# PIX_SH_V3D.net
KiCad netlist of a schematic drawn in Altium Designer
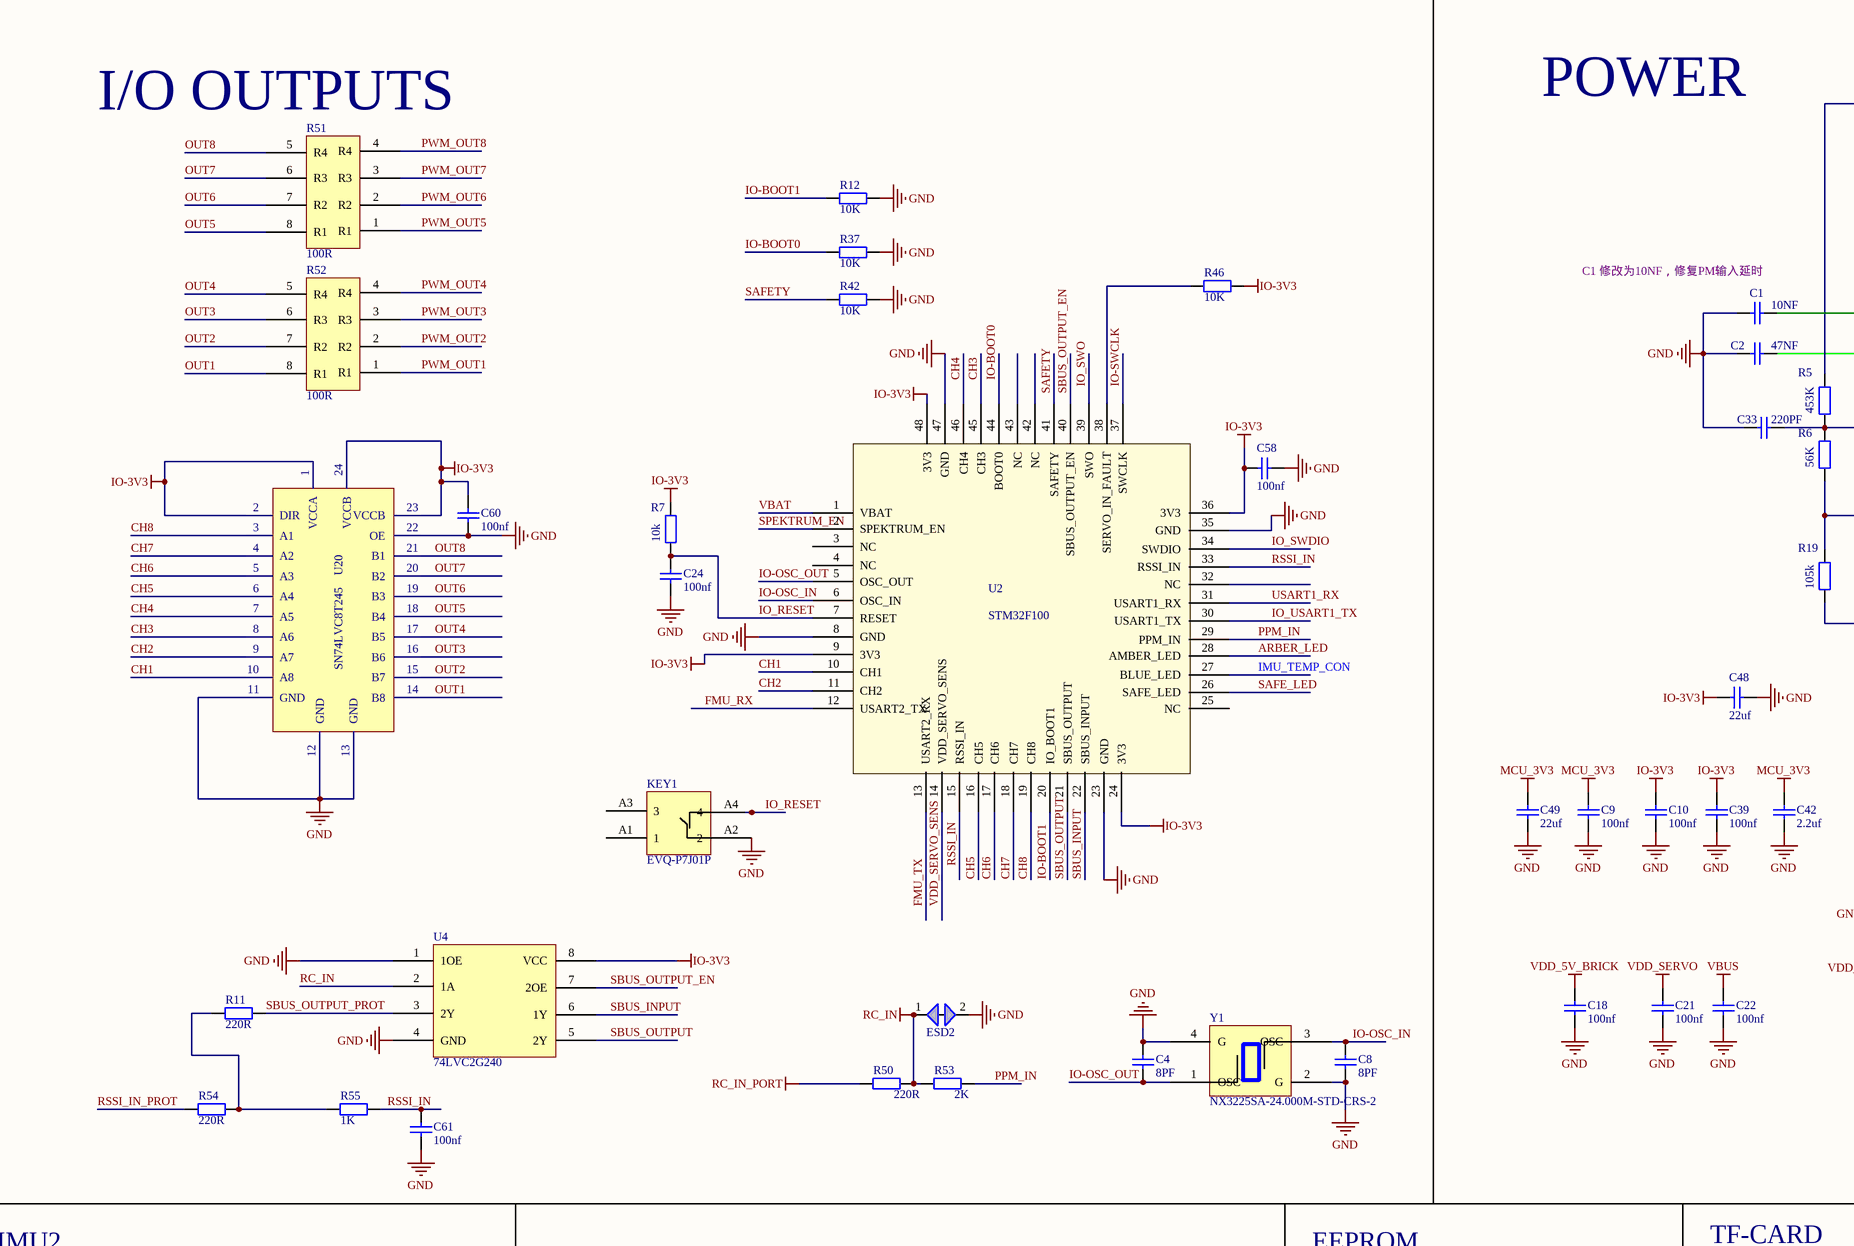
[diagram p0: PIX_SH_V3D.SchDoc, top left]
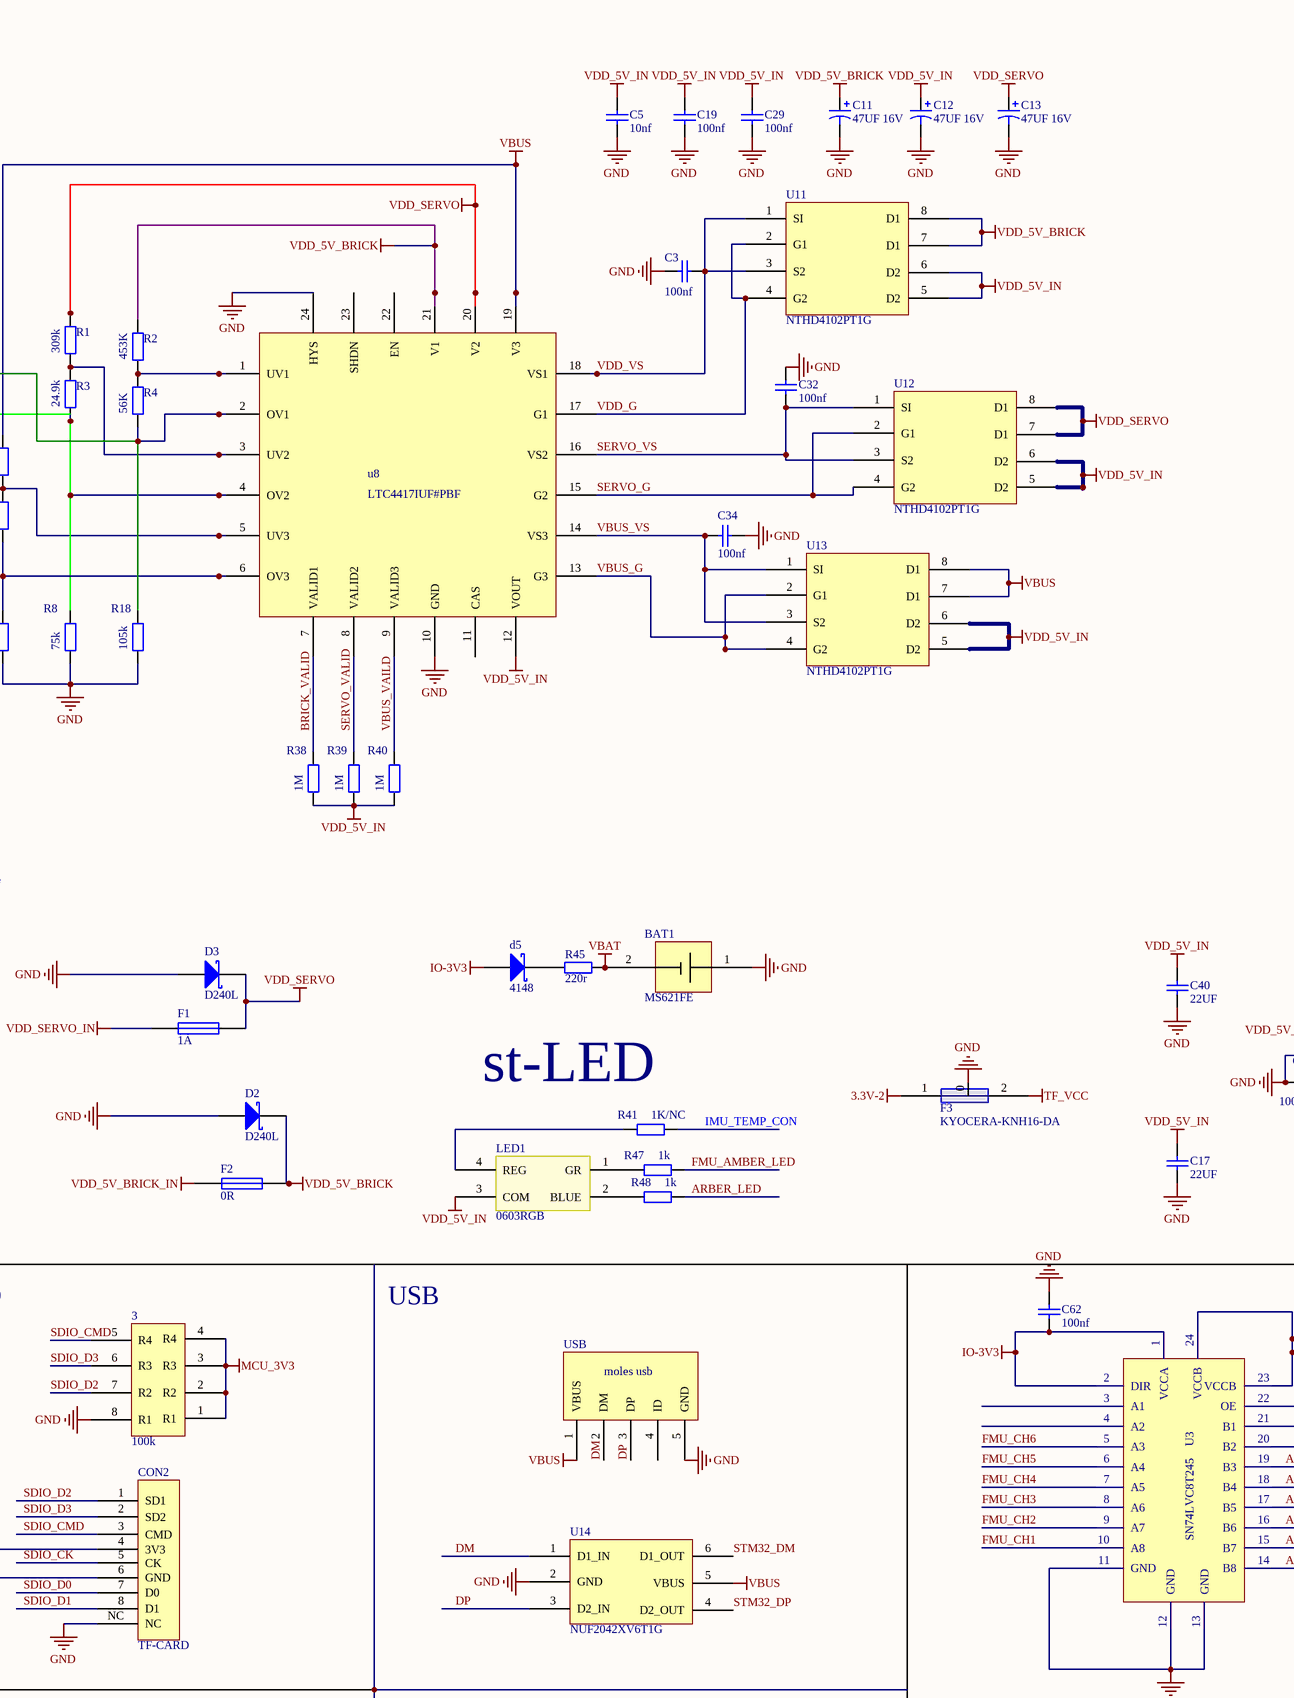
[diagram p1: PIX_SH_V3D.SchDoc, top middle]
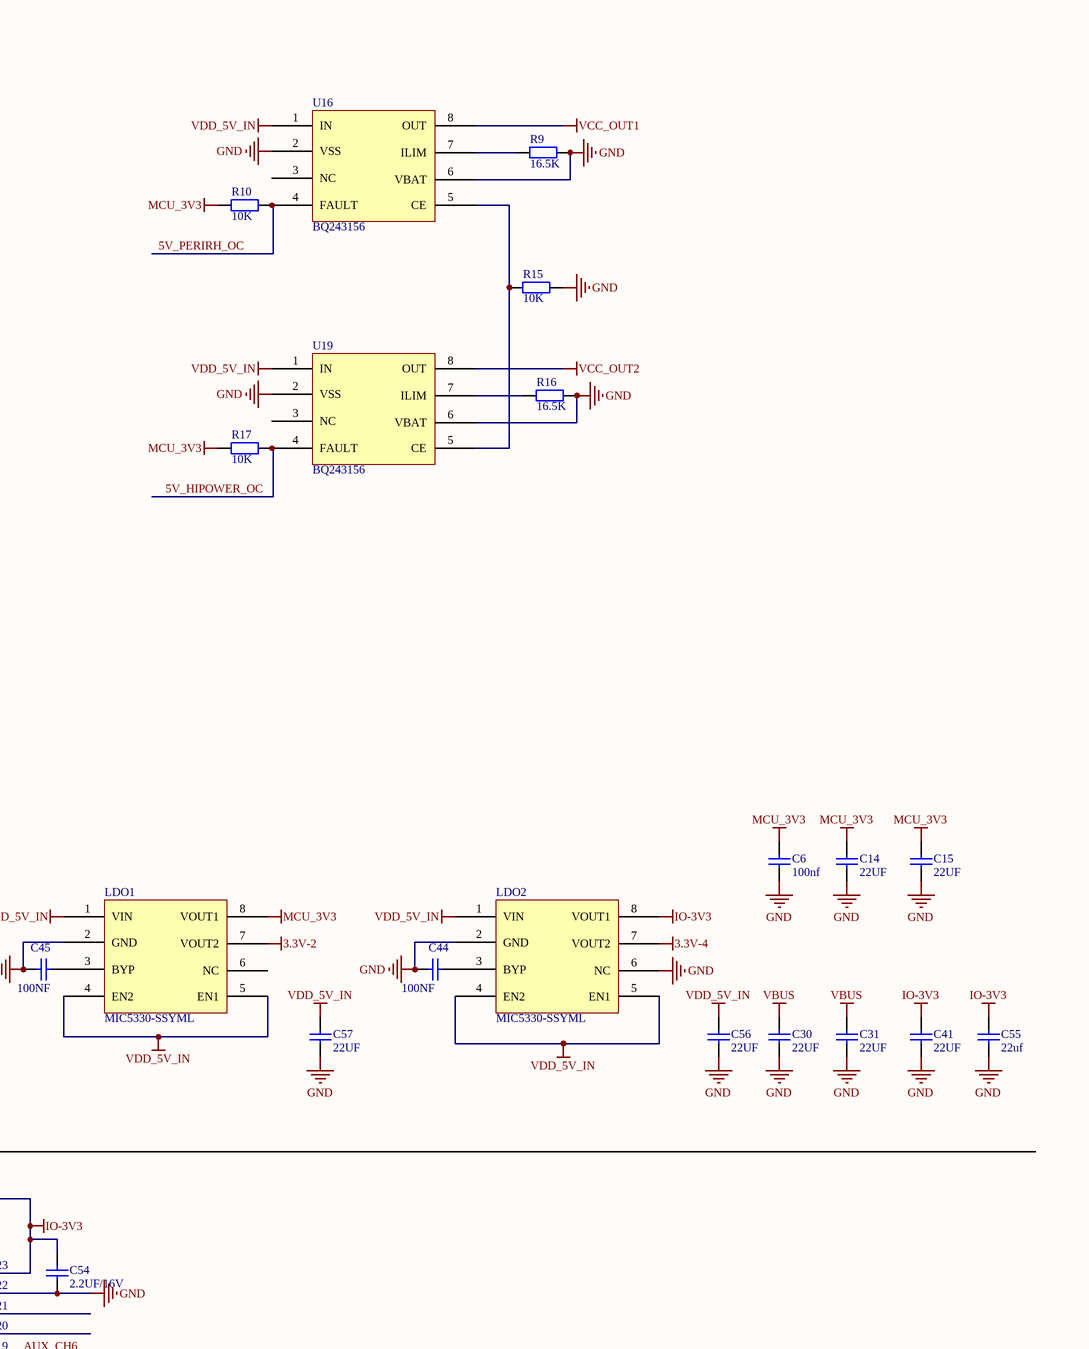
[diagram p2: PIX_SH_V3D.SchDoc, top right]
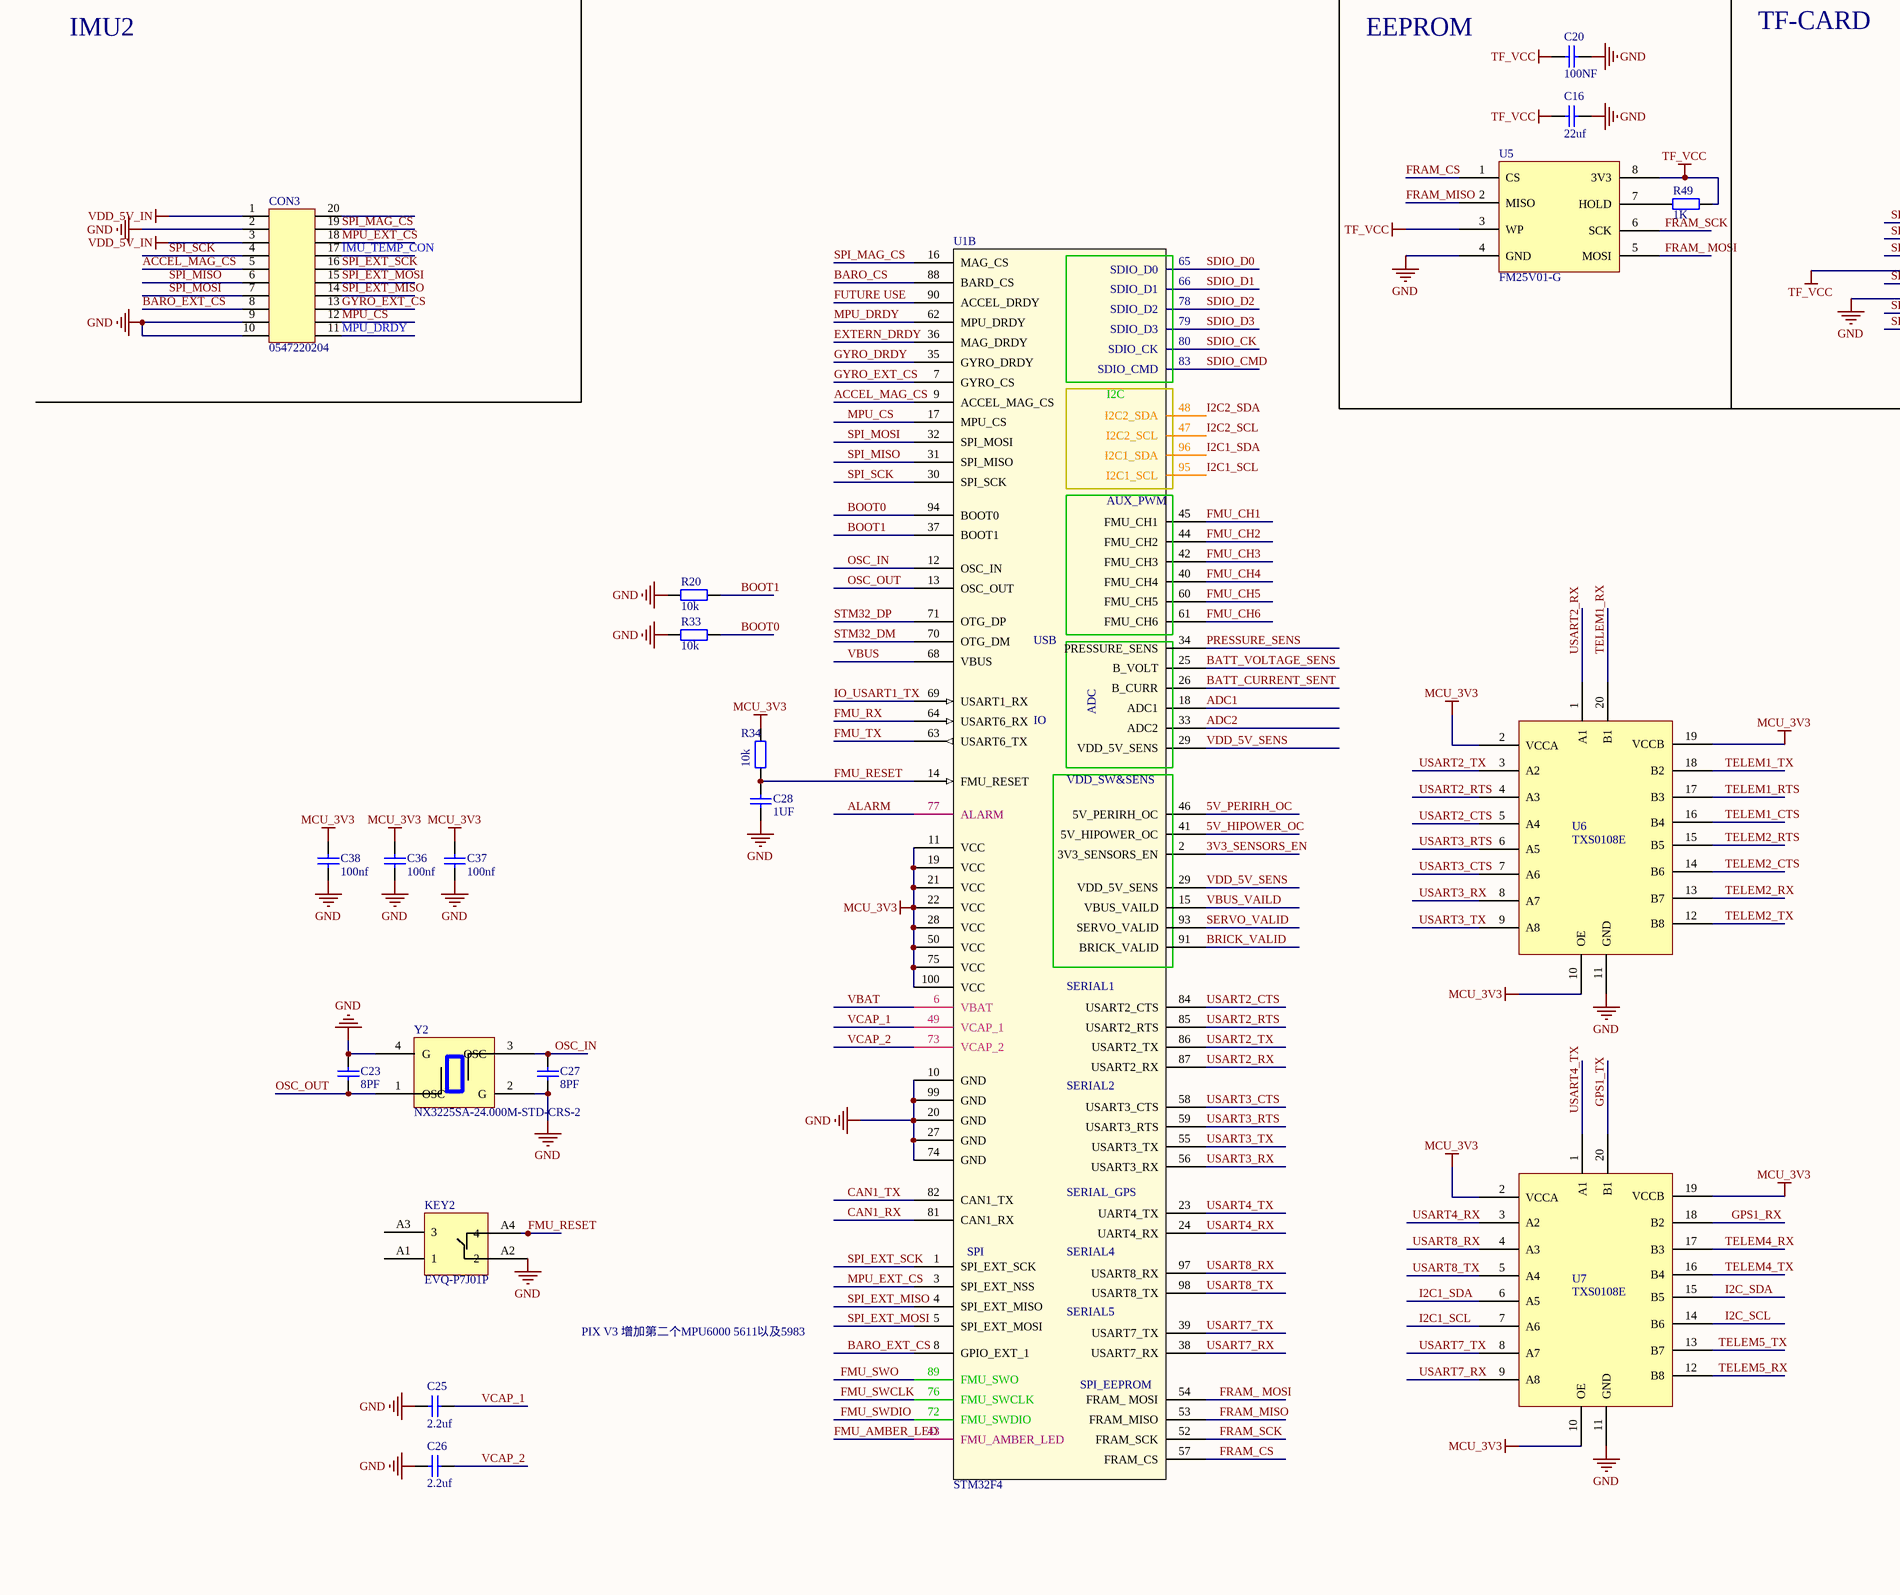
[diagram p3: PIX_SH_V3D.SchDoc, bottom left]
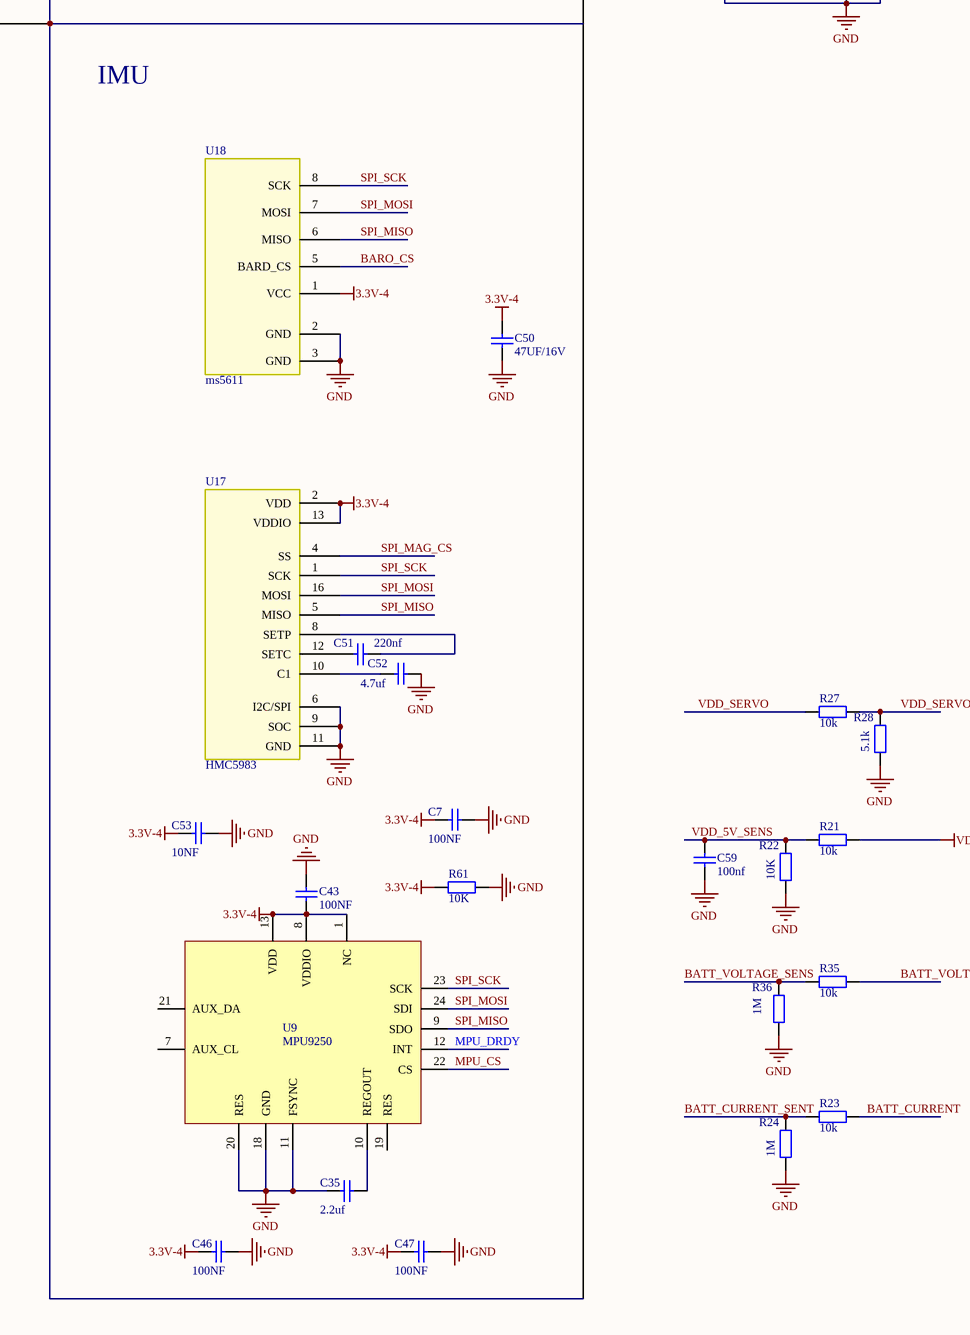
[diagram p4: PIX_SH_V3D.SchDoc, bottom middle]
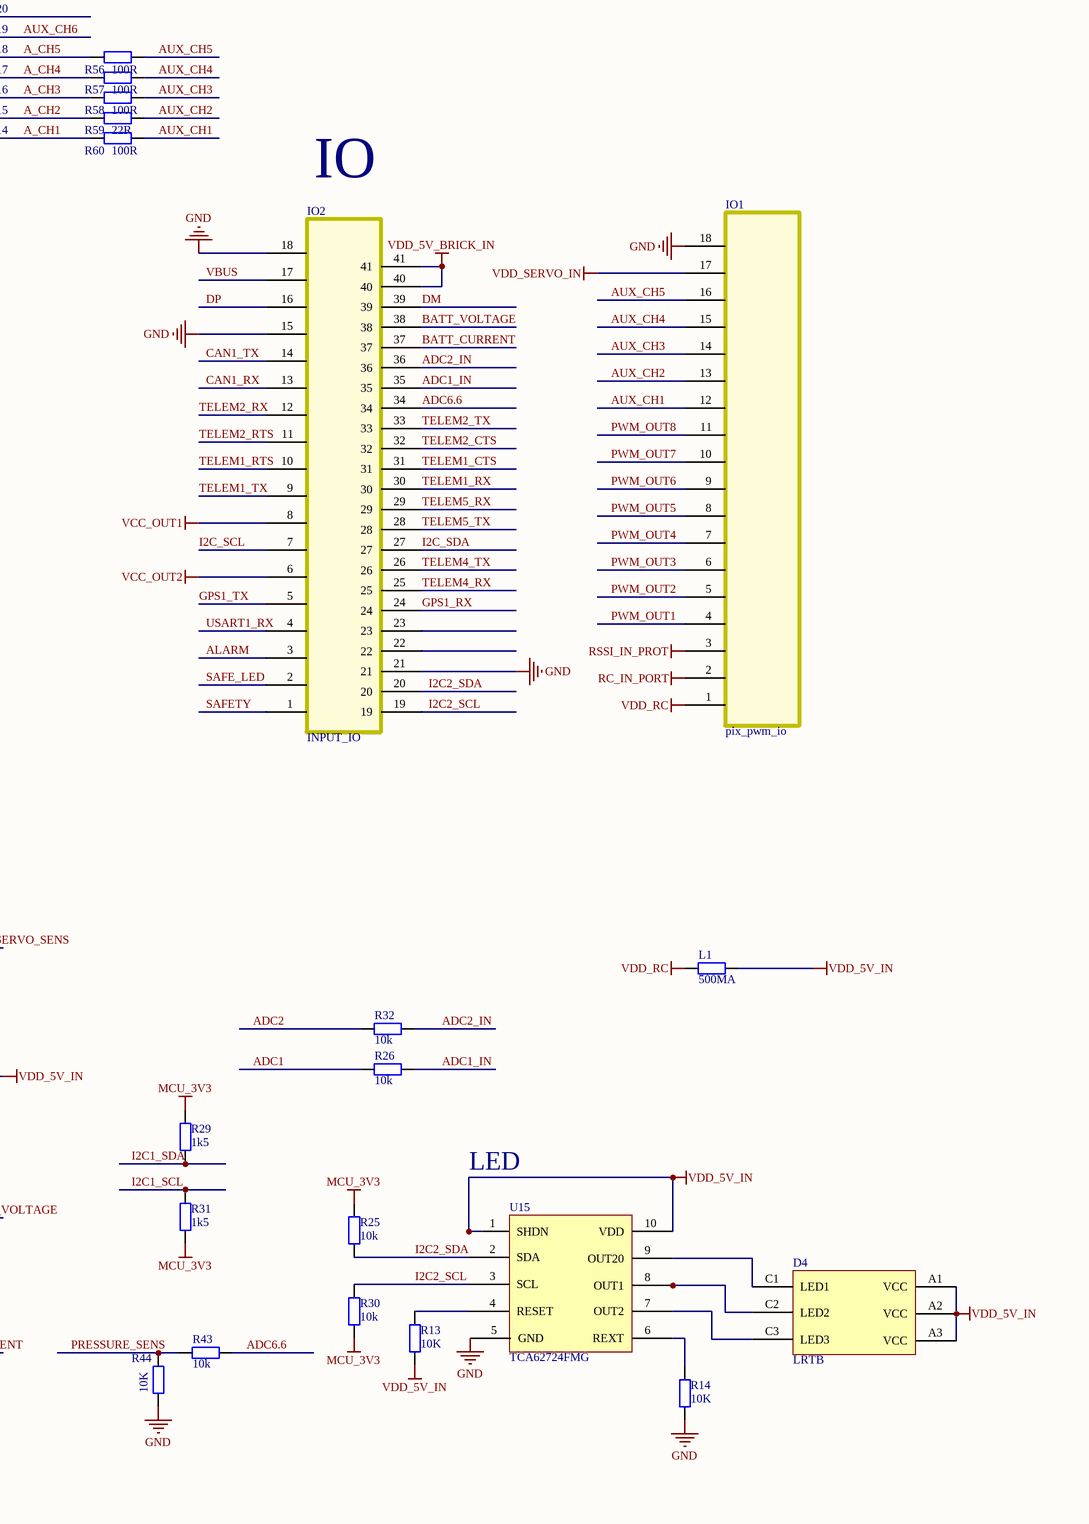
[diagram p5: PIX_SH_V3D.SchDoc, bottom right]

(export (version "E")
  (design (tool "Eeschema 10.0.6"))
  (components
    (comp (ref "3") (value "100k") (footprint "0402_4R") (libsource (lib "hack") (part "0402_4R")))
    (comp (ref "BAT1") (value "MS621FE") (footprint "MS621FE") (libsource (lib "hack") (part "MS621FE")))
    (comp (ref "C1")
      (value "10NF")
      (fields (field (name "PUBLISHER") "Altium Limited"))
      (libsource (lib "Miscellaneous Devices") (part "Cap"))
    )
    (comp (ref "C2")
      (value "47NF")
      (fields (field (name "PUBLISHER") "Altium Limited"))
      (libsource (lib "Miscellaneous Devices") (part "Cap"))
    )
    (comp (ref "C3")
      (value "100nf")
      (fields (field (name "PUBLISHER") "Altium Limited"))
      (libsource (lib "Miscellaneous Devices") (part "Cap"))
    )
    (comp (ref "C4")
      (value "8PF")
      (fields (field (name "PUBLISHER") "Altium Limited"))
      (libsource (lib "Miscellaneous Devices") (part "Cap"))
    )
    (comp (ref "C5")
      (value "10nf")
      (fields (field (name "PUBLISHER") "Altium Limited"))
      (libsource (lib "Miscellaneous Devices") (part "Cap"))
    )
    (comp (ref "C6")
      (value "100nf")
      (fields (field (name "PUBLISHER") "Altium Limited"))
      (libsource (lib "Miscellaneous Devices") (part "Cap"))
    )
    (comp (ref "C7")
      (value "100NF")
      (description "Capacitor")
      (fields (field (name "PUBLISHER") "Altium Limited"))
      (libsource (lib "Miscellaneous Devices") (part "Cap"))
    )
    (comp (ref "C8")
      (value "8PF")
      (fields (field (name "PUBLISHER") "Altium Limited"))
      (libsource (lib "Miscellaneous Devices") (part "Cap"))
    )
    (comp (ref "C9")
      (value "100nf")
      (fields (field (name "PUBLISHER") "Altium Limited"))
      (libsource (lib "Miscellaneous Devices") (part "Cap"))
    )
    (comp (ref "C10")
      (value "100nf")
      (fields (field (name "PUBLISHER") "Altium Limited"))
      (libsource (lib "Miscellaneous Devices") (part "Cap"))
    )
    (comp (ref "C11")
      (value "47UF 16V")
      (footprint "7343CAP")
      (description "Polarized Capacitor (Radial)")
      (fields (field (name "PUBLISHER") "Altium Limited"))
      (libsource (lib "Miscellaneous Devices") (part "Cap Pol1"))
    )
    (comp (ref "C12")
      (value "47UF 16V")
      (footprint "7343CAP")
      (description "Polarized Capacitor (Radial)")
      (fields (field (name "PUBLISHER") "Altium Limited"))
      (libsource (lib "Miscellaneous Devices") (part "Cap Pol1"))
    )
    (comp (ref "C13")
      (value "47UF 16V")
      (footprint "7343CAP")
      (description "Polarized Capacitor (Radial)")
      (fields (field (name "PUBLISHER") "Altium Limited"))
      (libsource (lib "Miscellaneous Devices") (part "Cap Pol1"))
    )
    (comp (ref "C14")
      (value "22UF")
      (fields (field (name "PUBLISHER") "Altium Limited"))
      (libsource (lib "Miscellaneous Devices") (part "Cap"))
    )
    (comp (ref "C15")
      (value "22UF")
      (fields (field (name "PUBLISHER") "Altium Limited"))
      (libsource (lib "Miscellaneous Devices") (part "Cap"))
    )
    (comp (ref "C16")
      (value "22uf")
      (fields (field (name "PUBLISHER") "Altium Limited"))
      (libsource (lib "Miscellaneous Devices") (part "Cap"))
    )
    (comp (ref "C17")
      (value "22UF")
      (fields (field (name "PUBLISHER") "Altium Limited"))
      (libsource (lib "Miscellaneous Devices") (part "Cap"))
    )
    (comp (ref "C18")
      (value "100nf")
      (fields (field (name "PUBLISHER") "Altium Limited"))
      (libsource (lib "Miscellaneous Devices") (part "Cap"))
    )
    (comp (ref "C19")
      (value "100nf")
      (fields (field (name "PUBLISHER") "Altium Limited"))
      (libsource (lib "Miscellaneous Devices") (part "Cap"))
    )
    (comp (ref "C20")
      (value "100NF")
      (fields (field (name "PUBLISHER") "Altium Limited"))
      (libsource (lib "Miscellaneous Devices") (part "Cap"))
    )
    (comp (ref "C21")
      (value "100nf")
      (fields (field (name "PUBLISHER") "Altium Limited"))
      (libsource (lib "Miscellaneous Devices") (part "Cap"))
    )
    (comp (ref "C22")
      (value "100nf")
      (fields (field (name "PUBLISHER") "Altium Limited"))
      (libsource (lib "Miscellaneous Devices") (part "Cap"))
    )
    (comp (ref "C23")
      (value "8PF")
      (fields (field (name "PUBLISHER") "Altium Limited"))
      (libsource (lib "Miscellaneous Devices") (part "Cap"))
    )
    (comp (ref "C24")
      (value "100nf")
      (fields (field (name "PUBLISHER") "Altium Limited"))
      (libsource (lib "Miscellaneous Devices") (part "Cap"))
    )
    (comp (ref "C25")
      (value "2.2uf")
      (fields (field (name "PUBLISHER") "Altium Limited"))
      (libsource (lib "Miscellaneous Devices") (part "Cap"))
    )
    (comp (ref "C26")
      (value "2.2uf")
      (fields (field (name "PUBLISHER") "Altium Limited"))
      (libsource (lib "Miscellaneous Devices") (part "Cap"))
    )
    (comp (ref "C27")
      (value "8PF")
      (fields (field (name "PUBLISHER") "Altium Limited"))
      (libsource (lib "Miscellaneous Devices") (part "Cap"))
    )
    (comp (ref "C28")
      (value "1UF")
      (fields (field (name "PUBLISHER") "Altium Limited"))
      (libsource (lib "Miscellaneous Devices") (part "Cap"))
    )
    (comp (ref "C29")
      (value "100nf")
      (fields (field (name "PUBLISHER") "Altium Limited"))
      (libsource (lib "Miscellaneous Devices") (part "Cap"))
    )
    (comp (ref "C30")
      (value "22UF")
      (fields (field (name "PUBLISHER") "Altium Limited"))
      (libsource (lib "Miscellaneous Devices") (part "Cap"))
    )
    (comp (ref "C31")
      (value "22UF")
      (fields (field (name "PUBLISHER") "Altium Limited"))
      (libsource (lib "Miscellaneous Devices") (part "Cap"))
    )
    (comp (ref "C32")
      (value "100nf")
      (fields (field (name "PUBLISHER") "Altium Limited"))
      (libsource (lib "Miscellaneous Devices") (part "Cap"))
    )
    (comp (ref "C33")
      (value "220PF")
      (fields (field (name "PUBLISHER") "Altium Limited"))
      (libsource (lib "Miscellaneous Devices") (part "Cap"))
    )
    (comp (ref "C34")
      (value "100nf")
      (fields (field (name "PUBLISHER") "Altium Limited"))
      (libsource (lib "Miscellaneous Devices") (part "Cap"))
    )
    (comp (ref "C35")
      (value "2.2uf")
      (description "Capacitor")
      (fields (field (name "PUBLISHER") "Altium Limited"))
      (libsource (lib "Miscellaneous Devices") (part "Cap"))
    )
    (comp (ref "C36")
      (value "100nf")
      (fields (field (name "PUBLISHER") "Altium Limited"))
      (libsource (lib "Miscellaneous Devices") (part "Cap"))
    )
    (comp (ref "C37")
      (value "100nf")
      (fields (field (name "PUBLISHER") "Altium Limited"))
      (libsource (lib "Miscellaneous Devices") (part "Cap"))
    )
    (comp (ref "C38")
      (value "100nf")
      (fields (field (name "PUBLISHER") "Altium Limited"))
      (libsource (lib "Miscellaneous Devices") (part "Cap"))
    )
    (comp (ref "C39")
      (value "100nf")
      (fields (field (name "PUBLISHER") "Altium Limited"))
      (libsource (lib "Miscellaneous Devices") (part "Cap"))
    )
    (comp (ref "C40")
      (value "22UF")
      (fields (field (name "PUBLISHER") "Altium Limited"))
      (libsource (lib "Miscellaneous Devices") (part "Cap"))
    )
    (comp (ref "C41")
      (value "22UF")
      (fields (field (name "PUBLISHER") "Altium Limited"))
      (libsource (lib "Miscellaneous Devices") (part "Cap"))
    )
    (comp (ref "C42")
      (value "2.2uf")
      (fields (field (name "PUBLISHER") "Altium Limited"))
      (libsource (lib "Miscellaneous Devices") (part "Cap"))
    )
    (comp (ref "C43")
      (value "100NF")
      (description "Capacitor")
      (fields (field (name "PUBLISHER") "Altium Limited"))
      (libsource (lib "Miscellaneous Devices") (part "Cap"))
    )
    (comp (ref "C44")
      (value "100NF")
      (fields (field (name "PUBLISHER") "Altium Limited"))
      (libsource (lib "Miscellaneous Devices") (part "Cap"))
    )
    (comp (ref "C45")
      (value "100NF")
      (fields (field (name "PUBLISHER") "Altium Limited"))
      (libsource (lib "Miscellaneous Devices") (part "Cap"))
    )
    (comp (ref "C46")
      (value "100NF")
      (description "Capacitor")
      (fields (field (name "PUBLISHER") "Altium Limited"))
      (libsource (lib "Miscellaneous Devices") (part "Cap"))
    )
    (comp (ref "C47")
      (value "100NF")
      (description "Capacitor")
      (fields (field (name "PUBLISHER") "Altium Limited"))
      (libsource (lib "Miscellaneous Devices") (part "Cap"))
    )
    (comp (ref "C48")
      (value "22uf")
      (fields (field (name "PUBLISHER") "Altium Limited"))
      (libsource (lib "Miscellaneous Devices") (part "Cap"))
    )
    (comp (ref "C49")
      (value "22uf")
      (fields (field (name "PUBLISHER") "Altium Limited"))
      (libsource (lib "Miscellaneous Devices") (part "Cap"))
    )
    (comp (ref "C50")
      (value "47UF/16V")
      (fields (field (name "PUBLISHER") "Altium Limited"))
      (libsource (lib "Miscellaneous Devices") (part "Cap"))
    )
    (comp (ref "C51")
      (value "220nf")
      (description "Capacitor")
      (fields (field (name "PUBLISHER") "Altium Limited"))
      (libsource (lib "Miscellaneous Devices") (part "Cap"))
    )
    (comp (ref "C52")
      (value "4.7uf")
      (description "Capacitor")
      (fields (field (name "PUBLISHER") "Altium Limited"))
      (libsource (lib "Miscellaneous Devices") (part "Cap"))
    )
    (comp (ref "C53")
      (value "10NF")
      (description "Capacitor")
      (fields (field (name "PUBLISHER") "Altium Limited"))
      (libsource (lib "Miscellaneous Devices") (part "Cap"))
    )
    (comp (ref "C54")
      (value "2.2UF/16V")
      (fields (field (name "PUBLISHER") "Altium Limited"))
      (libsource (lib "Miscellaneous Devices") (part "Cap"))
    )
    (comp (ref "C55")
      (value "22uf")
      (fields (field (name "PUBLISHER") "Altium Limited"))
      (libsource (lib "Miscellaneous Devices") (part "Cap"))
    )
    (comp (ref "C56")
      (value "22UF")
      (fields (field (name "PUBLISHER") "Altium Limited"))
      (libsource (lib "Miscellaneous Devices") (part "Cap"))
    )
    (comp (ref "C57")
      (value "22UF")
      (fields (field (name "PUBLISHER") "Altium Limited"))
      (libsource (lib "Miscellaneous Devices") (part "Cap"))
    )
    (comp (ref "C58")
      (value "100nf")
      (fields (field (name "PUBLISHER") "Altium Limited"))
      (libsource (lib "Miscellaneous Devices") (part "Cap"))
    )
    (comp (ref "C59")
      (value "100nf")
      (fields (field (name "PUBLISHER") "Altium Limited"))
      (libsource (lib "Miscellaneous Devices") (part "Cap"))
    )
    (comp (ref "C60")
      (value "100nf")
      (fields (field (name "PUBLISHER") "Altium Limited"))
      (libsource (lib "Miscellaneous Devices") (part "Cap"))
    )
    (comp (ref "C61")
      (value "100nf")
      (fields (field (name "PUBLISHER") "Altium Limited"))
      (libsource (lib "Miscellaneous Devices") (part "Cap"))
    )
    (comp (ref "C62")
      (value "100nf")
      (fields (field (name "PUBLISHER") "Altium Limited"))
      (libsource (lib "Miscellaneous Devices") (part "Cap"))
    )
    (comp (ref "CON2")
      (value "TF-CARD")
      (footprint "47352-1001")
      (libsource (lib "hack") (part "47352-1001"))
    )
    (comp (ref "CON3")
      (value "0547220204")
      (footprint "0547220204")
      (libsource (lib "CUAV") (part "0547220204"))
    )
    (comp (ref "D2")
      (value "D240L")
      (footprint "SOD-123")
      (description "Schottky Diode")
      (fields (field (name "PUBLISHER") "Altium Limited"))
      (libsource (lib "Miscellaneous Devices") (part "D Schottky"))
    )
    (comp (ref "D3")
      (value "D240L")
      (footprint "SOD-123")
      (description "Schottky Diode")
      (fields (field (name "PUBLISHER") "Altium Limited"))
      (libsource (lib "Miscellaneous Devices") (part "D Schottky"))
    )
    (comp (ref "D4") (value "LRTB") (footprint "LRTB") (libsource (lib "hack") (part "LRTB")))
    (comp (ref "d5")
      (value "4148")
      (footprint "SOD323")
      (description "Schottky Diode")
      (fields (field (name "PUBLISHER") "Altium Limited"))
      (libsource (lib "Miscellaneous Devices") (part "D Schottky"))
    )
    (comp (ref "ESD2") (value "DNP") (footprint "ESD0402") (libsource (lib "ONE BOX") (part "ESD0402")))
    (comp (ref "F1")
      (value "1A")
      (footprint "0805L")
      (description "Fuse")
      (fields (field (name "PUBLISHER") "Altium Limited"))
      (libsource (lib "Miscellaneous Devices") (part "Fuse 1"))
    )
    (comp (ref "F2")
      (value "0R")
      (footprint "0805L")
      (description "Fuse")
      (fields (field (name "PUBLISHER") "Altium Limited"))
      (libsource (lib "Miscellaneous Devices") (part "Fuse 1"))
    )
    (comp (ref "F3")
      (value "KYOCERA-KNH16-DA")
      (footprint "KYOCERA-KNH16-DA")
      (libsource (lib "hack") (part "KYOCERA-KNH16-DA"))
    )
    (comp (ref "IO1")
      (value "pix_pwm_io")
      (footprint "pix_pwm_out")
      (libsource (lib "hack") (part "pix_pwm_io"))
    )
    (comp (ref "IO2") (value "INPUT_IO") (footprint "PIX_OP") (libsource (lib "hack") (part "INPUT_IO")))
    (comp (ref "KEY1")
      (value "EVQ-P7J01P")
      (footprint "EVQ-P7J01P")
      (libsource (lib "hack") (part "EVQ-P7J01P"))
    )
    (comp (ref "KEY2")
      (value "EVQ-P7J01P")
      (footprint "EVQ-P7J01P")
      (libsource (lib "hack") (part "EVQ-P7J01P"))
    )
    (comp (ref "L1") (value "500MA") (description "Resistor") (libsource (lib "") (part "Res2_1")))
    (comp (ref "LDO1")
      (value "MIC5330-SSYML")
      (footprint "MIC5530")
      (libsource (lib "hack") (part "MIC5530"))
    )
    (comp (ref "LDO2")
      (value "MIC5330-SSYML")
      (footprint "MIC5530")
      (libsource (lib "hack") (part "MIC5530"))
    )
    (comp (ref "LED1") (value "0603RGB") (footprint "0603RGB") (libsource (lib "hack") (part "0603RGB")))
    (comp (ref "R1")
      (value "309k")
      (description "Resistor")
      (fields (field (name "PUBLISHER") "Altium Limited"))
      (libsource (lib "Miscellaneous Devices") (part "Res2"))
    )
    (comp (ref "R2")
      (value "453K")
      (description "Resistor")
      (fields (field (name "PUBLISHER") "Altium Limited"))
      (libsource (lib "Miscellaneous Devices") (part "Res2"))
    )
    (comp (ref "R3")
      (value "24.9k")
      (description "Resistor")
      (fields (field (name "PUBLISHER") "Altium Limited"))
      (libsource (lib "Miscellaneous Devices") (part "Res2"))
    )
    (comp (ref "R4")
      (value "56K")
      (description "Resistor")
      (fields (field (name "PUBLISHER") "Altium Limited"))
      (libsource (lib "Miscellaneous Devices") (part "Res2"))
    )
    (comp (ref "R5")
      (value "453K")
      (description "Resistor")
      (fields (field (name "PUBLISHER") "Altium Limited"))
      (libsource (lib "Miscellaneous Devices") (part "Res2"))
    )
    (comp (ref "R6")
      (value "56K")
      (description "Resistor")
      (fields (field (name "PUBLISHER") "Altium Limited"))
      (libsource (lib "Miscellaneous Devices") (part "Res2"))
    )
    (comp (ref "R7")
      (value "10k")
      (description "Resistor")
      (fields (field (name "PUBLISHER") "Altium Limited"))
      (libsource (lib "Miscellaneous Devices") (part "Res2"))
    )
    (comp (ref "R8")
      (value "75k")
      (description "Resistor")
      (fields (field (name "PUBLISHER") "Altium Limited"))
      (libsource (lib "Miscellaneous Devices") (part "Res2"))
    )
    (comp (ref "R9")
      (value "16.5K")
      (description "Resistor")
      (fields (field (name "PUBLISHER") "Altium Limited"))
      (libsource (lib "") (part "Res2_2"))
    )
    (comp (ref "R10")
      (value "10K")
      (description "Resistor")
      (fields (field (name "PUBLISHER") "Altium Limited"))
      (libsource (lib "") (part "Res2_1"))
    )
    (comp (ref "R11")
      (value "220R")
      (description "Resistor")
      (fields (field (name "PUBLISHER") "Altium Limited"))
      (libsource (lib "") (part "Res2_2"))
    )
    (comp (ref "R12")
      (value "10K")
      (description "Resistor")
      (fields (field (name "PUBLISHER") "Altium Limited"))
      (libsource (lib "") (part "Res2_2"))
    )
    (comp (ref "R13")
      (value "10K")
      (description "Resistor")
      (fields (field (name "PUBLISHER") "Altium Limited"))
      (libsource (lib "Miscellaneous Devices") (part "Res2"))
    )
    (comp (ref "R14")
      (value "10K")
      (description "Resistor")
      (fields (field (name "PUBLISHER") "Altium Limited"))
      (libsource (lib "Miscellaneous Devices") (part "Res2"))
    )
    (comp (ref "R15")
      (value "10K")
      (description "Resistor")
      (fields (field (name "PUBLISHER") "Altium Limited"))
      (libsource (lib "") (part "Res2_1"))
    )
    (comp (ref "R16")
      (value "16.5K")
      (description "Resistor")
      (fields (field (name "PUBLISHER") "Altium Limited"))
      (libsource (lib "") (part "Res2_1"))
    )
    (comp (ref "R17")
      (value "10K")
      (description "Resistor")
      (fields (field (name "PUBLISHER") "Altium Limited"))
      (libsource (lib "") (part "Res2_1"))
    )
    (comp (ref "R18")
      (value "105k")
      (description "Resistor")
      (fields (field (name "PUBLISHER") "Altium Limited"))
      (libsource (lib "Miscellaneous Devices") (part "Res2"))
    )
    (comp (ref "R19")
      (value "105k")
      (description "Resistor")
      (fields (field (name "PUBLISHER") "Altium Limited"))
      (libsource (lib "Miscellaneous Devices") (part "Res2"))
    )
    (comp (ref "R20")
      (value "10k")
      (description "Resistor")
      (fields (field (name "PUBLISHER") "Altium Limited"))
      (libsource (lib "") (part "Res2_2"))
    )
    (comp (ref "R21")
      (value "10k")
      (description "Resistor")
      (fields (field (name "PUBLISHER") "Altium Limited"))
      (libsource (lib "") (part "Res2_1"))
    )
    (comp (ref "R22")
      (value "10K")
      (description "Resistor")
      (fields (field (name "PUBLISHER") "Altium Limited"))
      (libsource (lib "Miscellaneous Devices") (part "Res2"))
    )
    (comp (ref "R23")
      (value "10k")
      (description "Resistor")
      (fields (field (name "PUBLISHER") "Altium Limited"))
      (libsource (lib "") (part "Res2_1"))
    )
    (comp (ref "R24")
      (value "1M")
      (description "Resistor")
      (fields (field (name "PUBLISHER") "Altium Limited"))
      (libsource (lib "Miscellaneous Devices") (part "Res2"))
    )
    (comp (ref "R25")
      (value "10k")
      (description "Resistor")
      (fields (field (name "PUBLISHER") "Altium Limited"))
      (libsource (lib "") (part "Res2_3"))
    )
    (comp (ref "R26")
      (value "10k")
      (description "Resistor")
      (fields (field (name "PUBLISHER") "Altium Limited"))
      (libsource (lib "") (part "Res2_1"))
    )
    (comp (ref "R27")
      (value "10k")
      (description "Resistor")
      (fields (field (name "PUBLISHER") "Altium Limited"))
      (libsource (lib "") (part "Res2_1"))
    )
    (comp (ref "R28")
      (value "5.1k")
      (description "Resistor")
      (fields (field (name "PUBLISHER") "Altium Limited"))
      (libsource (lib "Miscellaneous Devices") (part "Res2"))
    )
    (comp (ref "R29")
      (value "1k5")
      (description "Resistor")
      (fields (field (name "PUBLISHER") "Altium Limited"))
      (libsource (lib "") (part "Res2_3"))
    )
    (comp (ref "R30")
      (value "10k")
      (description "Resistor")
      (fields (field (name "PUBLISHER") "Altium Limited"))
      (libsource (lib "Miscellaneous Devices") (part "Res2"))
    )
    (comp (ref "R31")
      (value "1k5")
      (description "Resistor")
      (fields (field (name "PUBLISHER") "Altium Limited"))
      (libsource (lib "Miscellaneous Devices") (part "Res2"))
    )
    (comp (ref "R32")
      (value "10k")
      (description "Resistor")
      (fields (field (name "PUBLISHER") "Altium Limited"))
      (libsource (lib "") (part "Res2_1"))
    )
    (comp (ref "R33")
      (value "10k")
      (description "Resistor")
      (fields (field (name "PUBLISHER") "Altium Limited"))
      (libsource (lib "") (part "Res2_2"))
    )
    (comp (ref "R34")
      (value "10k")
      (description "Resistor")
      (fields (field (name "PUBLISHER") "Altium Limited"))
      (libsource (lib "Miscellaneous Devices") (part "Res2"))
    )
    (comp (ref "R35")
      (value "10k")
      (description "Resistor")
      (fields (field (name "PUBLISHER") "Altium Limited"))
      (libsource (lib "") (part "Res2_1"))
    )
    (comp (ref "R36")
      (value "1M")
      (description "Resistor")
      (fields (field (name "PUBLISHER") "Altium Limited"))
      (libsource (lib "Miscellaneous Devices") (part "Res2"))
    )
    (comp (ref "R37")
      (value "10K")
      (description "Resistor")
      (fields (field (name "PUBLISHER") "Altium Limited"))
      (libsource (lib "") (part "Res2_2"))
    )
    (comp (ref "R38")
      (value "1M")
      (description "Resistor")
      (fields (field (name "PUBLISHER") "Altium Limited"))
      (libsource (lib "Miscellaneous Devices") (part "Res2"))
    )
    (comp (ref "R39")
      (value "1M")
      (description "Resistor")
      (fields (field (name "PUBLISHER") "Altium Limited"))
      (libsource (lib "Miscellaneous Devices") (part "Res2"))
    )
    (comp (ref "R40")
      (value "1M")
      (description "Resistor")
      (fields (field (name "PUBLISHER") "Altium Limited"))
      (libsource (lib "Miscellaneous Devices") (part "Res2"))
    )
    (comp (ref "R41")
      (value "1K/NC")
      (description "Resistor")
      (fields (field (name "PUBLISHER") "Altium Limited"))
      (libsource (lib "") (part "Res2_1"))
    )
    (comp (ref "R42")
      (value "10K")
      (description "Resistor")
      (fields (field (name "PUBLISHER") "Altium Limited"))
      (libsource (lib "") (part "Res2_2"))
    )
    (comp (ref "R43")
      (value "10k")
      (description "Resistor")
      (fields (field (name "PUBLISHER") "Altium Limited"))
      (libsource (lib "") (part "Res2_1"))
    )
    (comp (ref "R44")
      (value "10K")
      (description "Resistor")
      (fields (field (name "PUBLISHER") "Altium Limited"))
      (libsource (lib "Miscellaneous Devices") (part "Res2"))
    )
    (comp (ref "R45")
      (value "220r")
      (description "Resistor")
      (fields (field (name "PUBLISHER") "Altium Limited"))
      (libsource (lib "") (part "Res2_1"))
    )
    (comp (ref "R46")
      (value "10K")
      (description "Resistor")
      (fields (field (name "PUBLISHER") "Altium Limited"))
      (libsource (lib "") (part "Res2_2"))
    )
    (comp (ref "R47")
      (value "1k")
      (description "Resistor")
      (fields (field (name "PUBLISHER") "Altium Limited"))
      (libsource (lib "") (part "Res2_1"))
    )
    (comp (ref "R48")
      (value "1k")
      (description "Resistor")
      (fields (field (name "PUBLISHER") "Altium Limited"))
      (libsource (lib "") (part "Res2_1"))
    )
    (comp (ref "R49")
      (value "1K")
      (description "Resistor")
      (fields (field (name "PUBLISHER") "Altium Limited"))
      (libsource (lib "") (part "Res2_2"))
    )
    (comp (ref "R50")
      (value "220R")
      (description "Resistor")
      (fields (field (name "PUBLISHER") "Altium Limited"))
      (libsource (lib "") (part "Res2_1"))
    )
    (comp (ref "R51") (value "100R") (footprint "0402_4R") (libsource (lib "hack") (part "0402_4R")))
    (comp (ref "R52") (value "100R") (footprint "0402_4R") (libsource (lib "hack") (part "0402_4R")))
    (comp (ref "R53")
      (value "2K")
      (description "Resistor")
      (fields (field (name "PUBLISHER") "Altium Limited"))
      (libsource (lib "") (part "Res2_1"))
    )
    (comp (ref "R54")
      (value "220R")
      (description "Resistor")
      (fields (field (name "PUBLISHER") "Altium Limited"))
      (libsource (lib "") (part "Res2_2"))
    )
    (comp (ref "R55")
      (value "1K")
      (description "Resistor")
      (fields (field (name "PUBLISHER") "Altium Limited"))
      (libsource (lib "") (part "Res2_2"))
    )
    (comp (ref "R56")
      (value "100R")
      (description "Resistor")
      (fields (field (name "PUBLISHER") "Altium Limited"))
      (libsource (lib "") (part "Res2_1"))
    )
    (comp (ref "R57")
      (value "100R")
      (description "Resistor")
      (fields (field (name "PUBLISHER") "Altium Limited"))
      (libsource (lib "") (part "Res2_1"))
    )
    (comp (ref "R58")
      (value "100R")
      (description "Resistor")
      (fields (field (name "PUBLISHER") "Altium Limited"))
      (libsource (lib "") (part "Res2_1"))
    )
    (comp (ref "R59")
      (value "22R")
      (description "Resistor")
      (fields (field (name "PUBLISHER") "Altium Limited"))
      (libsource (lib "") (part "Res2_1"))
    )
    (comp (ref "R60")
      (value "100R")
      (description "Resistor")
      (fields (field (name "PUBLISHER") "Altium Limited"))
      (libsource (lib "") (part "Res2_1"))
    )
    (comp (ref "R61") (value "10K") (description "Resistor") (libsource (lib "") (part "Res2_2")))
    (comp (ref "U1") (value "STM32F4") (footprint "TQFP100_2") (libsource (lib "hack") (part "STM32F4")))
    (comp (ref "U2") (value "STM32F100") (footprint "TQFP48") (libsource (lib "hack") (part "STM32F100")))
    (comp (ref "U3")
      (value "SN74LVC8T245")
      (footprint "QFN24-RGY")
      (libsource (lib "CUAV") (part "SN74LVC8T245"))
    )
    (comp (ref "U4")
      (value "74LVC2G240")
      (footprint "TSSOP8 - duplicate")
      (libsource (lib "hack") (part "74LVC2G240"))
    )
    (comp (ref "U5") (value "FM25V01-G") (footprint "SO-8") (libsource (lib "hack") (part "Component_1")))
    (comp (ref "U6") (value "TXS0108E") (footprint "QFN20-RGY") (libsource (lib "hack") (part "TXS0108E")))
    (comp (ref "U7") (value "TXS0108E") (footprint "QFN20-RGY") (libsource (lib "hack") (part "TXS0108E")))
    (comp (ref "u8")
      (value "LTC4417IUF#PBF")
      (footprint "QFN24")
      (libsource (lib "hack") (part "LTC4417IUF#PBF"))
    )
    (comp (ref "U9") (value "MPU9250") (footprint "QFN24-0.4") (libsource (lib "hack") (part "MPU9250")))
    (comp (ref "U11")
      (value "NTHD4102PT1G")
      (footprint "1206A?03")
      (libsource (lib "hack") (part "NTHD4102PT1G"))
    )
    (comp (ref "U12")
      (value "NTHD4102PT1G")
      (footprint "1206A?03")
      (libsource (lib "hack") (part "NTHD4102PT1G"))
    )
    (comp (ref "U13")
      (value "NTHD4102PT1G")
      (footprint "1206A?03")
      (libsource (lib "hack") (part "NTHD4102PT1G"))
    )
    (comp (ref "U14")
      (value "NUF2042XV6T1G")
      (footprint "SOT563-6")
      (libsource (lib "hack") (part "NUF2042XV6T1G"))
    )
    (comp (ref "U15") (value "TCA62724FMG") (footprint "SON10") (libsource (lib "hack") (part "TCA62724FMG")))
    (comp (ref "U16") (value "BQ243156") (footprint "QFN8") (libsource (lib "hack") (part "BQ243156")))
    (comp (ref "U17") (value "HMC5983") (footprint "HMC5983") (libsource (lib "hack") (part "HMC5983")))
    (comp (ref "U18") (value "ms5611") (footprint "ms5611") (libsource (lib "hack") (part "ms5611")))
    (comp (ref "U19") (value "BQ243156") (footprint "QFN8") (libsource (lib "hack") (part "BQ243156")))
    (comp (ref "U20")
      (value "SN74LVC8T245")
      (footprint "QFN24-RGY")
      (libsource (lib "CUAV") (part "SN74LVC8T245"))
    )
    (comp (ref "USB")
      (value "moles usb")
      (footprint "moles usb")
      (libsource (lib "XYUSB1") (part "moles usb"))
    )
    (comp (ref "Y1")
      (value "NX3225SA-24.000M-STD-CRS-2")
      (footprint "TSX-3225")
      (libsource (lib "hack") (part "TSX-3225"))
    )
    (comp (ref "Y2")
      (value "NX3225SA-24.000M-STD-CRS-2")
      (footprint "TSX-3225")
      (libsource (lib "hack") (part "TSX-3225"))
    )
  )
  (nets
    (net (code "1") (name "/3V3_SENSORS_EN") (class "Default")
      (node (ref "U1") (pin "2") (pinfunction "3V3_SENSORS_EN_2") (pintype "passive"))
    )
    (net (code "2") (name "/5V_HIPOWER_OC") (class "Default")
      (node (ref "R17") (pin "2") (pinfunction "2_2") (pintype "passive"))
      (node (ref "U1") (pin "41") (pinfunction "5V_HIPOWER_OC_41") (pintype "passive"))
      (node (ref "U19") (pin "4") (pinfunction "FAULT_4") (pintype "passive"))
    )
    (net (code "3") (name "/5V_PERIRH_OC") (class "Default")
      (node (ref "R10") (pin "2") (pinfunction "2_2") (pintype "passive"))
      (node (ref "U1") (pin "46") (pinfunction "5V_PERIRH_OC_46") (pintype "passive"))
      (node (ref "U16") (pin "4") (pinfunction "FAULT_4") (pintype "passive"))
    )
    (net (code "4") (name "/ACCEL_MAG_CS") (class "Default")
      (node (ref "CON3") (pin "5") (pinfunction "4_5") (pintype "passive"))
      (node (ref "U1") (pin "9") (pinfunction "ACCEL_MAG_CS_9") (pintype "passive"))
    )
    (net (code "5") (name "/ADC1") (class "Default")
      (node (ref "R26") (pin "1") (pinfunction "1_1") (pintype "passive"))
      (node (ref "U1") (pin "18") (pinfunction "ADC1_18") (pintype "passive"))
    )
    (net (code "6") (name "/ADC1_IN") (class "Default")
      (node (ref "IO2") (pin "35") (pinfunction "35_35") (pintype "passive"))
      (node (ref "R26") (pin "2") (pinfunction "2_2") (pintype "passive"))
    )
    (net (code "7") (name "/ADC2") (class "Default")
      (node (ref "R32") (pin "1") (pinfunction "1_1") (pintype "passive"))
      (node (ref "U1") (pin "33") (pinfunction "ADC2_33") (pintype "passive"))
    )
    (net (code "8") (name "/ADC2_IN") (class "Default")
      (node (ref "IO2") (pin "36") (pinfunction "36_36") (pintype "passive"))
      (node (ref "R32") (pin "2") (pinfunction "2_2") (pintype "passive"))
    )
    (net (code "9") (name "/ADC6.6") (class "Default")
      (node (ref "IO2") (pin "34") (pinfunction "34_34") (pintype "passive"))
      (node (ref "R43") (pin "2") (pinfunction "2_2") (pintype "passive"))
    )
    (net (code "10") (name "/ALARM") (class "Default")
      (node (ref "IO2") (pin "3") (pintype "passive"))
      (node (ref "U1") (pin "77") (pinfunction "ALARM_77") (pintype "passive"))
    )
    (net (code "11") (name "/ARBER_LED") (class "Default")
      (node (ref "R48") (pin "2") (pinfunction "2_2") (pintype "passive"))
      (node (ref "U2") (pin "28") (pinfunction "AMBER_LED_28") (pintype "passive"))
    )
    (net (code "12") (name "/AUX_CH1") (class "Default")
      (node (ref "IO1") (pin "12") (pintype "passive"))
      (node (ref "R60") (pin "2") (pinfunction "2_2") (pintype "passive"))
    )
    (net (code "13") (name "/AUX_CH2") (class "Default")
      (node (ref "IO1") (pin "13") (pintype "passive"))
      (node (ref "R59") (pin "2") (pinfunction "2_2") (pintype "passive"))
    )
    (net (code "14") (name "/AUX_CH3") (class "Default")
      (node (ref "IO1") (pin "14") (pintype "passive"))
      (node (ref "R58") (pin "2") (pinfunction "2_2") (pintype "passive"))
    )
    (net (code "15") (name "/AUX_CH4") (class "Default")
      (node (ref "IO1") (pin "15") (pintype "passive"))
      (node (ref "R57") (pin "2") (pinfunction "2_2") (pintype "passive"))
    )
    (net (code "16") (name "/AUX_CH5") (class "Default")
      (node (ref "IO1") (pin "16") (pintype "passive"))
      (node (ref "R56") (pin "2") (pinfunction "2_2") (pintype "passive"))
    )
    (net (code "17") (name "/AUX_CH6") (class "Default")
      (node (ref "U3") (pin "19") (pinfunction "B3_19") (pintype "passive"))
    )
    (net (code "18") (name "/A_CH1") (class "Default")
      (node (ref "R60") (pin "1") (pinfunction "1_1") (pintype "passive"))
      (node (ref "U3") (pin "14") (pinfunction "B8_14") (pintype "passive"))
    )
    (net (code "19") (name "/A_CH2") (class "Default")
      (node (ref "R59") (pin "1") (pinfunction "1_1") (pintype "passive"))
      (node (ref "U3") (pin "15") (pinfunction "B7_15") (pintype "passive"))
    )
    (net (code "20") (name "/A_CH3") (class "Default")
      (node (ref "R58") (pin "1") (pinfunction "1_1") (pintype "passive"))
      (node (ref "U3") (pin "16") (pinfunction "B6_16") (pintype "passive"))
    )
    (net (code "21") (name "/A_CH4") (class "Default")
      (node (ref "R57") (pin "1") (pinfunction "1_1") (pintype "passive"))
      (node (ref "U3") (pin "17") (pinfunction "B5_17") (pintype "passive"))
    )
    (net (code "22") (name "/A_CH5") (class "Default")
      (node (ref "R56") (pin "1") (pinfunction "1_1") (pintype "passive"))
      (node (ref "U3") (pin "18") (pinfunction "B4_18") (pintype "passive"))
    )
    (net (code "23") (name "/BARO_CS") (class "Default")
      (node (ref "U1") (pin "88") (pinfunction "BARD_CS_88") (pintype "passive"))
      (node (ref "U18") (pin "5") (pinfunction "BARD_CS_5") (pintype "passive"))
    )
    (net (code "24") (name "/BARO_EXT_CS") (class "Default")
      (node (ref "CON3") (pin "8") (pinfunction "7_8") (pintype "passive"))
      (node (ref "U1") (pin "8") (pinfunction "GPIO_EXT_1_8") (pintype "passive"))
    )
    (net (code "25") (name "/BATT_CURRENT") (class "Default")
      (node (ref "IO2") (pin "37") (pinfunction "37_37") (pintype "passive"))
      (node (ref "R23") (pin "2") (pinfunction "2_2") (pintype "passive"))
    )
    (net (code "26") (name "/BATT_CURRENT_SENT") (class "Default")
      (node (ref "R23") (pin "1") (pinfunction "1_1") (pintype "passive"))
      (node (ref "R24") (pin "2") (pinfunction "2_2") (pintype "passive"))
      (node (ref "U1") (pin "26") (pinfunction "B_CURR_26") (pintype "passive"))
    )
    (net (code "27") (name "/BATT_VOLTAGE") (class "Default")
      (node (ref "IO2") (pin "38") (pinfunction "38_38") (pintype "passive"))
      (node (ref "R35") (pin "2") (pinfunction "2_2") (pintype "passive"))
    )
    (net (code "28") (name "/BATT_VOLTAGE_SENS") (class "Default")
      (node (ref "R35") (pin "1") (pinfunction "1_1") (pintype "passive"))
      (node (ref "R36") (pin "2") (pinfunction "2_2") (pintype "passive"))
      (node (ref "U1") (pin "25") (pinfunction "B_VOLT_25") (pintype "passive"))
    )
    (net (code "29") (name "/BOOT0") (class "Default")
      (node (ref "R33") (pin "1") (pinfunction "1_1") (pintype "passive"))
      (node (ref "U1") (pin "94") (pinfunction "BOOT0_94") (pintype "passive"))
    )
    (net (code "30") (name "/BOOT1") (class "Default")
      (node (ref "R20") (pin "1") (pinfunction "1_1") (pintype "passive"))
      (node (ref "U1") (pin "37") (pinfunction "BOOT1_37") (pintype "passive"))
    )
    (net (code "31") (name "/BRICK_VALID") (class "Default")
      (node (ref "R38") (pin "2") (pinfunction "2_2") (pintype "passive"))
      (node (ref "U1") (pin "91") (pinfunction "BRICK_VALID_91") (pintype "passive"))
      (node (ref "u8") (pin "7") (pinfunction "VALID1_7") (pintype "passive"))
    )
    (net (code "32") (name "/CAN1_RX") (class "Default")
      (node (ref "IO2") (pin "13") (pintype "passive"))
      (node (ref "U1") (pin "81") (pinfunction "CAN1_RX_81") (pintype "passive"))
    )
    (net (code "33") (name "/CAN1_TX") (class "Default")
      (node (ref "IO2") (pin "14") (pintype "passive"))
      (node (ref "U1") (pin "82") (pinfunction "CAN1_TX_82") (pintype "passive"))
    )
    (net (code "34") (name "/CH1") (class "Default")
      (node (ref "U2") (pin "10") (pinfunction "CH1_10") (pintype "passive"))
      (node (ref "U20") (pin "10") (pinfunction "A8_10") (pintype "passive"))
    )
    (net (code "35") (name "/CH2") (class "Default")
      (node (ref "U2") (pin "11") (pinfunction "CH2_11") (pintype "passive"))
      (node (ref "U20") (pin "9") (pinfunction "A7_9") (pintype "passive"))
    )
    (net (code "36") (name "/CH3") (class "Default")
      (node (ref "U2") (pin "45") (pinfunction "CH3_45") (pintype "passive"))
      (node (ref "U20") (pin "8") (pinfunction "A6_8") (pintype "passive"))
    )
    (net (code "37") (name "/CH4") (class "Default")
      (node (ref "U2") (pin "46") (pinfunction "CH4_46") (pintype "passive"))
      (node (ref "U20") (pin "7") (pinfunction "A5_7") (pintype "passive"))
    )
    (net (code "38") (name "/CH5") (class "Default")
      (node (ref "U2") (pin "16") (pinfunction "CH5_16") (pintype "passive"))
      (node (ref "U20") (pin "6") (pinfunction "A4_6") (pintype "passive"))
    )
    (net (code "39") (name "/CH6") (class "Default")
      (node (ref "U2") (pin "17") (pinfunction "CH6_17") (pintype "passive"))
      (node (ref "U20") (pin "5") (pinfunction "A3_5") (pintype "passive"))
    )
    (net (code "40") (name "/CH7") (class "Default")
      (node (ref "U2") (pin "18") (pinfunction "CH7_18") (pintype "passive"))
      (node (ref "U20") (pin "4") (pinfunction "A2_4") (pintype "passive"))
    )
    (net (code "41") (name "/CH8") (class "Default")
      (node (ref "U2") (pin "19") (pinfunction "CH8_19") (pintype "passive"))
      (node (ref "U20") (pin "3") (pinfunction "A1_3") (pintype "passive"))
    )
    (net (code "42") (name "/DM") (class "Default")
      (node (ref "IO2") (pin "39") (pinfunction "39_39") (pintype "passive"))
      (node (ref "U14") (pin "1") (pinfunction "D1_IN_1") (pintype "passive"))
      (node (ref "USB") (pin "2") (pinfunction "DM_2") (pintype "passive"))
    )
    (net (code "43") (name "/DP") (class "Default")
      (node (ref "IO2") (pin "16") (pintype "passive"))
      (node (ref "U14") (pin "3") (pinfunction "D2_IN_3") (pintype "passive"))
      (node (ref "USB") (pin "3") (pinfunction "DP_3") (pintype "passive"))
    )
    (net (code "44") (name "/EXTERN_DRDY") (class "Default")
      (node (ref "U1") (pin "36") (pinfunction "MAG_DRDY_36") (pintype "passive"))
    )
    (net (code "45") (name "/FMU_AMBER_LED") (class "Default")
      (node (ref "R47") (pin "2") (pinfunction "2_2") (pintype "passive"))
      (node (ref "U1") (pin "43") (pinfunction "FMU_AMBER_LED_43") (pintype "passive"))
    )
    (net (code "46") (name "/FMU_CH1") (class "Default")
      (node (ref "U1") (pin "45") (pinfunction "FMU_CH1_45") (pintype "passive"))
      (node (ref "U3") (pin "10") (pinfunction "A8_10") (pintype "passive"))
    )
    (net (code "47") (name "/FMU_CH2") (class "Default")
      (node (ref "U1") (pin "44") (pinfunction "FMU_CH2_44") (pintype "passive"))
      (node (ref "U3") (pin "9") (pinfunction "A7_9") (pintype "passive"))
    )
    (net (code "48") (name "/FMU_CH3") (class "Default")
      (node (ref "U1") (pin "42") (pinfunction "FMU_CH3_42") (pintype "passive"))
      (node (ref "U3") (pin "8") (pinfunction "A6_8") (pintype "passive"))
    )
    (net (code "49") (name "/FMU_CH4") (class "Default")
      (node (ref "U1") (pin "40") (pinfunction "FMU_CH4_40") (pintype "passive"))
      (node (ref "U3") (pin "7") (pinfunction "A5_7") (pintype "passive"))
    )
    (net (code "50") (name "/FMU_CH5") (class "Default")
      (node (ref "U1") (pin "60") (pinfunction "FMU_CH5_60") (pintype "passive"))
      (node (ref "U3") (pin "6") (pinfunction "A4_6") (pintype "passive"))
    )
    (net (code "51") (name "/FMU_CH6") (class "Default")
      (node (ref "U1") (pin "61") (pinfunction "FMU_CH6_61") (pintype "passive"))
      (node (ref "U3") (pin "5") (pinfunction "A3_5") (pintype "passive"))
    )
    (net (code "52") (name "/FMU_RESET") (class "Default")
      (node (ref "C28") (pin "2") (pinfunction "2_2") (pintype "passive"))
      (node (ref "KEY2") (pin "A4") (pinfunction "4_A4") (pintype "passive"))
      (node (ref "R34") (pin "1") (pinfunction "1_1") (pintype "passive"))
      (node (ref "U1") (pin "14") (pinfunction "FMU_RESET_14") (pintype "input"))
    )
    (net (code "53") (name "/FMU_RX") (class "Default")
      (node (ref "U1") (pin "64") (pinfunction "USART6_RX_64") (pintype "input"))
      (node (ref "U2") (pin "12") (pinfunction "USART2_TX_12") (pintype "passive"))
    )
    (net (code "54") (name "/FMU_SWCLK") (class "Default")
      (node (ref "U1") (pin "76") (pinfunction "FMU_SWCLK_76") (pintype "passive"))
    )
    (net (code "55") (name "/FMU_SWDIO") (class "Default")
      (node (ref "U1") (pin "72") (pinfunction "FMU_SWDIO_72") (pintype "passive"))
    )
    (net (code "56") (name "/FMU_SWO") (class "Default")
      (node (ref "U1") (pin "89") (pinfunction "FMU_SWO_89") (pintype "passive"))
    )
    (net (code "57") (name "/FMU_TX") (class "Default")
      (node (ref "U1") (pin "63") (pinfunction "USART6_TX_63") (pintype "output"))
      (node (ref "U2") (pin "13") (pinfunction "USART2_RX_13") (pintype "passive"))
    )
    (net (code "58") (name "/FRAM_ MOSI") (class "Default")
      (node (ref "U1") (pin "54") (pinfunction "FRAM__MOSI_54") (pintype "passive"))
      (node (ref "U5") (pin "5") (pinfunction "MOSI_5") (pintype "passive"))
    )
    (net (code "59") (name "/FRAM_CS") (class "Default")
      (node (ref "U1") (pin "57") (pinfunction "FRAM_CS_57") (pintype "passive"))
      (node (ref "U5") (pin "1") (pinfunction "CS_1") (pintype "passive"))
    )
    (net (code "60") (name "/FRAM_MISO") (class "Default")
      (node (ref "U1") (pin "53") (pinfunction "FRAM_MISO_53") (pintype "passive"))
      (node (ref "U5") (pin "2") (pinfunction "MISO_2") (pintype "passive"))
    )
    (net (code "61") (name "/FRAM_SCK") (class "Default")
      (node (ref "U1") (pin "52") (pinfunction "FRAM_SCK_52") (pintype "passive"))
      (node (ref "U5") (pin "6") (pinfunction "SCK_6") (pintype "passive"))
    )
    (net (code "62") (name "/FUTURE USE") (class "Default")
      (node (ref "U1") (pin "90") (pinfunction "ACCEL_DRDY_90") (pintype "passive"))
    )
    (net (code "63") (name "/GPS1_RX") (class "Default")
      (node (ref "IO2") (pin "24") (pinfunction "24_24") (pintype "passive"))
      (node (ref "U7") (pin "18") (pinfunction "B2_18") (pintype "passive"))
    )
    (net (code "64") (name "/GPS1_TX") (class "Default")
      (node (ref "IO2") (pin "5") (pintype "passive"))
      (node (ref "U7") (pin "20") (pinfunction "B1_20") (pintype "passive"))
    )
    (net (code "65") (name "/GYRO_DRDY") (class "Default")
      (node (ref "U1") (pin "35") (pinfunction "GYRO_DRDY_35") (pintype "passive"))
    )
    (net (code "66") (name "/GYRO_EXT_CS") (class "Default")
      (node (ref "CON3") (pin "13") (pinfunction "12_13") (pintype "passive"))
      (node (ref "U1") (pin "7") (pinfunction "GYRO_CS_7") (pintype "passive"))
    )
    (net (code "67") (name "/I2C1_SCL") (class "Default")
      (node (ref "R31") (pin "2") (pinfunction "2_2") (pintype "passive"))
      (node (ref "U1") (pin "95") (pinfunction "I2C1_SCL_95") (pintype "passive"))
      (node (ref "U7") (pin "7") (pinfunction "A6_7") (pintype "passive"))
    )
    (net (code "68") (name "/I2C1_SDA") (class "Default")
      (node (ref "R29") (pin "2") (pinfunction "2_2") (pintype "passive"))
      (node (ref "U1") (pin "96") (pinfunction "I2C1_SDA_96") (pintype "passive"))
      (node (ref "U7") (pin "6") (pinfunction "A5_6") (pintype "passive"))
    )
    (net (code "69") (name "/I2C2_SCL") (class "Default")
      (node (ref "IO2") (pin "19") (pinfunction "19_19") (pintype "passive"))
      (node (ref "R30") (pin "2") (pinfunction "2_2") (pintype "passive"))
      (node (ref "U1") (pin "47") (pinfunction "I2C2_SCL_47") (pintype "passive"))
      (node (ref "U15") (pin "3") (pinfunction "SCL_3") (pintype "passive"))
    )
    (net (code "70") (name "/I2C2_SDA") (class "Default")
      (node (ref "IO2") (pin "20") (pinfunction "20_20") (pintype "passive"))
      (node (ref "R25") (pin "2") (pinfunction "2_2") (pintype "passive"))
      (node (ref "U1") (pin "48") (pinfunction "I2C2_SDA_48") (pintype "passive"))
      (node (ref "U15") (pin "2") (pinfunction "SDA_2") (pintype "passive"))
    )
    (net (code "71") (name "/I2C_SCL") (class "Default")
      (node (ref "IO2") (pin "7") (pintype "passive"))
      (node (ref "U7") (pin "14") (pinfunction "B6_14") (pintype "passive"))
    )
    (net (code "72") (name "/I2C_SDA") (class "Default")
      (node (ref "IO2") (pin "27") (pinfunction "27_27") (pintype "passive"))
      (node (ref "U7") (pin "15") (pinfunction "B5_15") (pintype "passive"))
    )
    (net (code "73") (name "/IMU_TEMP_CON") (class "Default")
      (node (ref "CON3") (pin "17") (pinfunction "16_17") (pintype "passive"))
      (node (ref "R41") (pin "2") (pinfunction "2_2") (pintype "passive"))
      (node (ref "U2") (pin "27") (pinfunction "BLUE_LED_27") (pintype "passive"))
    )
    (net (code "74") (name "/IO-BOOT0") (class "Default")
      (node (ref "R37") (pin "2") (pinfunction "2_2") (pintype "passive"))
      (node (ref "U2") (pin "44") (pinfunction "BOOT0_44") (pintype "passive"))
    )
    (net (code "75") (name "/IO-BOOT1") (class "Default")
      (node (ref "R12") (pin "2") (pinfunction "2_2") (pintype "passive"))
      (node (ref "U2") (pin "20") (pinfunction "IO_BOOT1_20") (pintype "passive"))
    )
    (net (code "76") (name "/IO-OSC_IN") (class "Default")
      (node (ref "C8") (pin "2") (pinfunction "2_2") (pintype "passive"))
      (node (ref "U2") (pin "6") (pinfunction "OSC_IN_6") (pintype "passive"))
      (node (ref "Y1") (pin "3") (pinfunction "OSC_3") (pintype "passive"))
    )
    (net (code "77") (name "/IO-OSC_OUT") (class "Default")
      (node (ref "C4") (pin "1") (pinfunction "1_1") (pintype "passive"))
      (node (ref "U2") (pin "5") (pinfunction "OSC_OUT_5") (pintype "passive"))
      (node (ref "Y1") (pin "1") (pinfunction "OSC_1") (pintype "passive"))
    )
    (net (code "78") (name "/IO-SWCLK") (class "Default")
      (node (ref "U2") (pin "37") (pinfunction "SWCLK_37") (pintype "passive"))
    )
    (net (code "79") (name "/IO_RESET") (class "Default")
      (node (ref "C24") (pin "2") (pinfunction "2_2") (pintype "passive"))
      (node (ref "KEY1") (pin "A4") (pinfunction "4_A4") (pintype "passive"))
      (node (ref "R7") (pin "1") (pinfunction "1_1") (pintype "passive"))
      (node (ref "U2") (pin "7") (pinfunction "RESET_7") (pintype "passive"))
    )
    (net (code "80") (name "/IO_SWDIO") (class "Default")
      (node (ref "U2") (pin "34") (pinfunction "SWDIO_34") (pintype "passive"))
    )
    (net (code "81") (name "/IO_SWO") (class "Default")
      (node (ref "U2") (pin "39") (pinfunction "SWO_39") (pintype "passive"))
    )
    (net (code "82") (name "/IO_USART1_TX") (class "Default")
      (node (ref "U1") (pin "69") (pinfunction "USART1_RX_69") (pintype "input"))
      (node (ref "U2") (pin "30") (pinfunction "USART1_TX_30") (pintype "passive"))
    )
    (net (code "83") (name "/MPU_CS") (class "Default")
      (node (ref "CON3") (pin "12") (pinfunction "11_12") (pintype "passive"))
      (node (ref "U1") (pin "17") (pinfunction "MPU_CS_17") (pintype "passive"))
      (node (ref "U9") (pin "22") (pinfunction "CS_22") (pintype "passive"))
    )
    (net (code "84") (name "/MPU_DRDY") (class "Default")
      (node (ref "CON3") (pin "11") (pinfunction "10_11") (pintype "passive"))
      (node (ref "U1") (pin "62") (pinfunction "MPU_DRDY_62") (pintype "passive"))
      (node (ref "U9") (pin "12") (pinfunction "INT_12") (pintype "passive"))
    )
    (net (code "85") (name "/MPU_EXT_CS") (class "Default")
      (node (ref "CON3") (pin "18") (pinfunction "17_18") (pintype "passive"))
      (node (ref "U1") (pin "3") (pinfunction "SPI_EXT_NSS_3") (pintype "passive"))
    )
    (net (code "86") (name "/OSC_IN") (class "Default")
      (node (ref "C27") (pin "2") (pinfunction "2_2") (pintype "passive"))
      (node (ref "U1") (pin "12") (pinfunction "OSC_IN_12") (pintype "passive"))
      (node (ref "Y2") (pin "3") (pinfunction "OSC_3") (pintype "passive"))
    )
    (net (code "87") (name "/OSC_OUT") (class "Default")
      (node (ref "C23") (pin "1") (pinfunction "1_1") (pintype "passive"))
      (node (ref "U1") (pin "13") (pinfunction "OSC_OUT_13") (pintype "passive"))
      (node (ref "Y2") (pin "1") (pinfunction "OSC_1") (pintype "passive"))
    )
    (net (code "88") (name "/OUT1") (class "Default")
      (node (ref "R52") (pin "8") (pinfunction "R1_8") (pintype "passive"))
      (node (ref "U20") (pin "14") (pinfunction "B8_14") (pintype "passive"))
    )
    (net (code "89") (name "/OUT2") (class "Default")
      (node (ref "R52") (pin "7") (pinfunction "R2_7") (pintype "passive"))
      (node (ref "U20") (pin "15") (pinfunction "B7_15") (pintype "passive"))
    )
    (net (code "90") (name "/OUT3") (class "Default")
      (node (ref "R52") (pin "6") (pinfunction "R3_6") (pintype "passive"))
      (node (ref "U20") (pin "16") (pinfunction "B6_16") (pintype "passive"))
    )
    (net (code "91") (name "/OUT4") (class "Default")
      (node (ref "R52") (pin "5") (pinfunction "R4_5") (pintype "passive"))
      (node (ref "U20") (pin "17") (pinfunction "B5_17") (pintype "passive"))
    )
    (net (code "92") (name "/OUT5") (class "Default")
      (node (ref "R51") (pin "8") (pinfunction "R1_8") (pintype "passive"))
      (node (ref "U20") (pin "18") (pinfunction "B4_18") (pintype "passive"))
    )
    (net (code "93") (name "/OUT6") (class "Default")
      (node (ref "R51") (pin "7") (pinfunction "R2_7") (pintype "passive"))
      (node (ref "U20") (pin "19") (pinfunction "B3_19") (pintype "passive"))
    )
    (net (code "94") (name "/OUT7") (class "Default")
      (node (ref "R51") (pin "6") (pinfunction "R3_6") (pintype "passive"))
      (node (ref "U20") (pin "20") (pinfunction "B2_20") (pintype "passive"))
    )
    (net (code "95") (name "/OUT8") (class "Default")
      (node (ref "R51") (pin "5") (pinfunction "R4_5") (pintype "passive"))
      (node (ref "U20") (pin "21") (pinfunction "B1_21") (pintype "passive"))
    )
    (net (code "96") (name "/PPM_IN") (class "Default")
      (node (ref "R53") (pin "2") (pinfunction "2_2") (pintype "passive"))
      (node (ref "U2") (pin "29") (pinfunction "PPM_IN_29") (pintype "passive"))
    )
    (net (code "97") (name "/PRESSURE_SENS") (class "Default")
      (node (ref "R43") (pin "1") (pinfunction "1_1") (pintype "passive"))
      (node (ref "R44") (pin "2") (pinfunction "2_2") (pintype "passive"))
      (node (ref "U1") (pin "34") (pinfunction "PRESSURE_SENS_34") (pintype "passive"))
    )
    (net (code "98") (name "/PWM_OUT1") (class "Default")
      (node (ref "IO1") (pin "4") (pintype "passive"))
      (node (ref "R52") (pin "1") (pinfunction "R1_1") (pintype "passive"))
    )
    (net (code "99") (name "/PWM_OUT2") (class "Default")
      (node (ref "IO1") (pin "5") (pintype "passive"))
      (node (ref "R52") (pin "2") (pinfunction "R2_2") (pintype "passive"))
    )
    (net (code "100") (name "/PWM_OUT3") (class "Default")
      (node (ref "IO1") (pin "6") (pintype "passive"))
      (node (ref "R52") (pin "3") (pinfunction "R3_3") (pintype "passive"))
    )
    (net (code "101") (name "/PWM_OUT4") (class "Default")
      (node (ref "IO1") (pin "7") (pintype "passive"))
      (node (ref "R52") (pin "4") (pinfunction "R4_4") (pintype "passive"))
    )
    (net (code "102") (name "/PWM_OUT5") (class "Default")
      (node (ref "IO1") (pin "8") (pintype "passive"))
      (node (ref "R51") (pin "1") (pinfunction "R1_1") (pintype "passive"))
    )
    (net (code "103") (name "/PWM_OUT6") (class "Default")
      (node (ref "IO1") (pin "9") (pintype "passive"))
      (node (ref "R51") (pin "2") (pinfunction "R2_2") (pintype "passive"))
    )
    (net (code "104") (name "/PWM_OUT7") (class "Default")
      (node (ref "IO1") (pin "10") (pintype "passive"))
      (node (ref "R51") (pin "3") (pinfunction "R3_3") (pintype "passive"))
    )
    (net (code "105") (name "/PWM_OUT8") (class "Default")
      (node (ref "IO1") (pin "11") (pintype "passive"))
      (node (ref "R51") (pin "4") (pinfunction "R4_4") (pintype "passive"))
    )
    (net (code "106") (name "/RSSI_IN") (class "Default")
      (node (ref "C61") (pin "2") (pinfunction "2_2") (pintype "passive"))
      (node (ref "R55") (pin "1") (pinfunction "1_1") (pintype "passive"))
      (node (ref "U2") (pin "15") (pinfunction "RSSI_IN_15") (pintype "passive"))
      (node (ref "U2") (pin "33") (pinfunction "RSSI_IN_33") (pintype "passive"))
    )
    (net (code "107") (name "/SAFETY") (class "Default")
      (node (ref "IO2") (pin "1") (pintype "passive"))
      (node (ref "R42") (pin "2") (pinfunction "2_2") (pintype "passive"))
      (node (ref "U2") (pin "41") (pinfunction "SAFETY_41") (pintype "passive"))
    )
    (net (code "108") (name "/SAFE_LED") (class "Default")
      (node (ref "IO2") (pin "2") (pintype "passive"))
      (node (ref "U2") (pin "26") (pinfunction "SAFE_LED_26") (pintype "passive"))
    )
    (net (code "109") (name "/SBUS_INPUT") (class "Default")
      (node (ref "U2") (pin "22") (pinfunction "SBUS_INPUT_22") (pintype "passive"))
      (node (ref "U4") (pin "6") (pinfunction "1Y_6") (pintype "passive"))
    )
    (net (code "110") (name "/SBUS_OUTPUT") (class "Default")
      (node (ref "U2") (pin "21") (pinfunction "SBUS_OUTPUT_21") (pintype "passive"))
      (node (ref "U4") (pin "5") (pinfunction "2Y_5") (pintype "passive"))
    )
    (net (code "111") (name "/SBUS_OUTPUT_EN") (class "Default")
      (node (ref "U2") (pin "40") (pinfunction "SBUS_OUTPUT_EN_40") (pintype "passive"))
      (node (ref "U4") (pin "7") (pinfunction "2OE_7") (pintype "passive"))
    )
    (net (code "112") (name "/SBUS_OUTPUT_PROT") (class "Default")
      (node (ref "R11") (pin "1") (pinfunction "1_1") (pintype "passive"))
      (node (ref "U4") (pin "3") (pinfunction "2Y_3") (pintype "passive"))
    )
    (net (code "113") (name "/SDIO_CK") (class "Default")
      (node (ref "CON2") (pin "5") (pinfunction "CK_5") (pintype "passive"))
      (node (ref "U1") (pin "80") (pinfunction "SDIO_CK_80") (pintype "passive"))
    )
    (net (code "114") (name "/SDIO_CMD") (class "Default")
      (node (ref "3") (pin "5") (pinfunction "R4_5") (pintype "passive"))
      (node (ref "CON2") (pin "3") (pinfunction "CMD_3") (pintype "passive"))
      (node (ref "U1") (pin "83") (pinfunction "SDIO_CMD_83") (pintype "passive"))
    )
    (net (code "115") (name "/SDIO_D0") (class "Default")
      (node (ref "CON2") (pin "7") (pinfunction "D0_7") (pintype "passive"))
      (node (ref "U1") (pin "65") (pinfunction "SDIO_D0_65") (pintype "passive"))
    )
    (net (code "116") (name "/SDIO_D1") (class "Default")
      (node (ref "CON2") (pin "8") (pinfunction "D1_8") (pintype "passive"))
      (node (ref "U1") (pin "66") (pinfunction "SDIO_D1_66") (pintype "passive"))
    )
    (net (code "117") (name "/SDIO_D2") (class "Default")
      (node (ref "3") (pin "7") (pinfunction "R2_7") (pintype "passive"))
      (node (ref "CON2") (pin "1") (pinfunction "SD1_1") (pintype "passive"))
      (node (ref "U1") (pin "78") (pinfunction "SDIO_D2_78") (pintype "passive"))
    )
    (net (code "118") (name "/SDIO_D3") (class "Default")
      (node (ref "3") (pin "6") (pinfunction "R3_6") (pintype "passive"))
      (node (ref "CON2") (pin "2") (pinfunction "SD2_2") (pintype "passive"))
      (node (ref "U1") (pin "79") (pinfunction "SDIO_D3_79") (pintype "passive"))
    )
    (net (code "119") (name "/SERVO_G") (class "Default")
      (node (ref "U12") (pin "2") (pinfunction "G1_2") (pintype "passive"))
      (node (ref "U12") (pin "4") (pinfunction "G2_4") (pintype "passive"))
      (node (ref "u8") (pin "15") (pinfunction "G2_15") (pintype "passive"))
    )
    (net (code "120") (name "/SERVO_VALID") (class "Default")
      (node (ref "R39") (pin "2") (pinfunction "2_2") (pintype "passive"))
      (node (ref "U1") (pin "93") (pinfunction "SERVO_VALID_93") (pintype "passive"))
      (node (ref "u8") (pin "8") (pinfunction "VALID2_8") (pintype "passive"))
    )
    (net (code "121") (name "/SERVO_VS") (class "Default")
      (node (ref "C32") (pin "1") (pinfunction "1_1") (pintype "passive"))
      (node (ref "U12") (pin "1") (pinfunction "SI_1") (pintype "passive"))
      (node (ref "U12") (pin "3") (pinfunction "S2_3") (pintype "passive"))
      (node (ref "u8") (pin "16") (pinfunction "VS2_16") (pintype "passive"))
    )
    (net (code "122") (name "/SPEKTRUM_EN") (class "Default")
      (node (ref "U2") (pin "2") (pinfunction "SPEKTRUM_EN_2") (pintype "passive"))
    )
    (net (code "123") (name "/SPI_EXT_MISO") (class "Default")
      (node (ref "CON3") (pin "14") (pinfunction "13_14") (pintype "passive"))
      (node (ref "U1") (pin "4") (pinfunction "SPI_EXT_MISO_4") (pintype "passive"))
    )
    (net (code "124") (name "/SPI_EXT_MOSI") (class "Default")
      (node (ref "CON3") (pin "15") (pinfunction "14_15") (pintype "passive"))
      (node (ref "U1") (pin "5") (pinfunction "SPI_EXT_MOSI_5") (pintype "passive"))
    )
    (net (code "125") (name "/SPI_EXT_SCK") (class "Default")
      (node (ref "CON3") (pin "16") (pinfunction "15_16") (pintype "passive"))
      (node (ref "U1") (pin "1") (pinfunction "SPI_EXT_SCK_1") (pintype "passive"))
    )
    (net (code "126") (name "/SPI_MAG_CS") (class "Default")
      (node (ref "CON3") (pin "19") (pinfunction "18_19") (pintype "passive"))
      (node (ref "U1") (pin "16") (pinfunction "MAG_CS_16") (pintype "passive"))
      (node (ref "U17") (pin "4") (pinfunction "SS_4") (pintype "passive"))
    )
    (net (code "127") (name "/SPI_MISO") (class "Default")
      (node (ref "CON3") (pin "6") (pinfunction "5_6") (pintype "passive"))
      (node (ref "U1") (pin "31") (pinfunction "SPI_MISO_31") (pintype "passive"))
      (node (ref "U17") (pin "5") (pinfunction "MISO_5") (pintype "passive"))
      (node (ref "U18") (pin "6") (pinfunction "MISO_6") (pintype "passive"))
      (node (ref "U9") (pin "9") (pinfunction "SDO_9") (pintype "passive"))
    )
    (net (code "128") (name "/SPI_MOSI") (class "Default")
      (node (ref "CON3") (pin "7") (pinfunction "6_7") (pintype "passive"))
      (node (ref "U1") (pin "32") (pinfunction "SPI_MOSI_32") (pintype "passive"))
      (node (ref "U17") (pin "16") (pinfunction "MOSI_16") (pintype "passive"))
      (node (ref "U18") (pin "7") (pinfunction "MOSI_7") (pintype "passive"))
      (node (ref "U9") (pin "24") (pinfunction "SDI_24") (pintype "passive"))
    )
    (net (code "129") (name "/SPI_SCK") (class "Default")
      (node (ref "CON3") (pin "4") (pinfunction "3_4") (pintype "passive"))
      (node (ref "U1") (pin "30") (pinfunction "SPI_SCK_30") (pintype "passive"))
      (node (ref "U17") (pin "1") (pinfunction "SCK_1") (pintype "passive"))
      (node (ref "U18") (pin "8") (pinfunction "SCK_8") (pintype "passive"))
      (node (ref "U9") (pin "23") (pinfunction "SCK_23") (pintype "passive"))
    )
    (net (code "130") (name "/STM32_DM") (class "Default")
      (node (ref "U1") (pin "70") (pinfunction "OTG_DM_70") (pintype "passive"))
      (node (ref "U14") (pin "6") (pinfunction "D1_OUT_6") (pintype "passive"))
    )
    (net (code "131") (name "/STM32_DP") (class "Default")
      (node (ref "U1") (pin "71") (pinfunction "OTG_DP_71") (pintype "passive"))
      (node (ref "U14") (pin "4") (pinfunction "D2_OUT_4") (pintype "passive"))
    )
    (net (code "132") (name "/TELEM1_CTS") (class "Default")
      (node (ref "IO2") (pin "31") (pinfunction "31_31") (pintype "passive"))
      (node (ref "U6") (pin "16") (pinfunction "B4_16") (pintype "passive"))
    )
    (net (code "133") (name "/TELEM1_RTS") (class "Default")
      (node (ref "IO2") (pin "10") (pintype "passive"))
      (node (ref "U6") (pin "17") (pinfunction "B3_17") (pintype "passive"))
    )
    (net (code "134") (name "/TELEM1_RX") (class "Default")
      (node (ref "IO2") (pin "30") (pinfunction "30_30") (pintype "passive"))
      (node (ref "U6") (pin "20") (pinfunction "B1_20") (pintype "passive"))
    )
    (net (code "135") (name "/TELEM1_TX") (class "Default")
      (node (ref "IO2") (pin "9") (pintype "passive"))
      (node (ref "U6") (pin "18") (pinfunction "B2_18") (pintype "passive"))
    )
    (net (code "136") (name "/TELEM2_CTS") (class "Default")
      (node (ref "IO2") (pin "32") (pinfunction "32_32") (pintype "passive"))
      (node (ref "U6") (pin "14") (pinfunction "B6_14") (pintype "passive"))
    )
    (net (code "137") (name "/TELEM2_RTS") (class "Default")
      (node (ref "IO2") (pin "11") (pintype "passive"))
      (node (ref "U6") (pin "15") (pinfunction "B5_15") (pintype "passive"))
    )
    (net (code "138") (name "/TELEM2_RX") (class "Default")
      (node (ref "IO2") (pin "12") (pintype "passive"))
      (node (ref "U6") (pin "13") (pinfunction "B7_13") (pintype "passive"))
    )
    (net (code "139") (name "/TELEM2_TX") (class "Default")
      (node (ref "IO2") (pin "33") (pinfunction "33_33") (pintype "passive"))
      (node (ref "U6") (pin "12") (pinfunction "B8_12") (pintype "passive"))
    )
    (net (code "140") (name "/TELEM4_RX") (class "Default")
      (node (ref "IO2") (pin "25") (pinfunction "25_25") (pintype "passive"))
      (node (ref "U7") (pin "17") (pinfunction "B3_17") (pintype "passive"))
    )
    (net (code "141") (name "/TELEM4_TX") (class "Default")
      (node (ref "IO2") (pin "26") (pinfunction "26_26") (pintype "passive"))
      (node (ref "U7") (pin "16") (pinfunction "B4_16") (pintype "passive"))
    )
    (net (code "142") (name "/TELEM5_RX") (class "Default")
      (node (ref "IO2") (pin "29") (pinfunction "29_29") (pintype "passive"))
      (node (ref "U7") (pin "12") (pinfunction "B8_12") (pintype "passive"))
    )
    (net (code "143") (name "/TELEM5_TX") (class "Default")
      (node (ref "IO2") (pin "28") (pinfunction "28_28") (pintype "passive"))
      (node (ref "U7") (pin "13") (pinfunction "B7_13") (pintype "passive"))
    )
    (net (code "144") (name "/USART1_RX") (class "Default")
      (node (ref "IO2") (pin "4") (pintype "passive"))
      (node (ref "U2") (pin "31") (pinfunction "USART1_RX_31") (pintype "passive"))
    )
    (net (code "145") (name "/USART2_CTS") (class "Default")
      (node (ref "U1") (pin "84") (pinfunction "USART2_CTS_84") (pintype "passive"))
      (node (ref "U6") (pin "5") (pinfunction "A4_5") (pintype "passive"))
    )
    (net (code "146") (name "/USART2_RTS") (class "Default")
      (node (ref "U1") (pin "85") (pinfunction "USART2_RTS_85") (pintype "passive"))
      (node (ref "U6") (pin "4") (pinfunction "A3_4") (pintype "passive"))
    )
    (net (code "147") (name "/USART2_RX") (class "Default")
      (node (ref "U1") (pin "87") (pinfunction "USART2_RX_87") (pintype "passive"))
      (node (ref "U6") (pin "1") (pinfunction "A1_1") (pintype "passive"))
    )
    (net (code "148") (name "/USART2_TX") (class "Default")
      (node (ref "U1") (pin "86") (pinfunction "USART2_TX_86") (pintype "passive"))
      (node (ref "U6") (pin "3") (pinfunction "A2_3") (pintype "passive"))
    )
    (net (code "149") (name "/USART3_CTS") (class "Default")
      (node (ref "U1") (pin "58") (pinfunction "USART3_CTS_58") (pintype "passive"))
      (node (ref "U6") (pin "7") (pinfunction "A6_7") (pintype "passive"))
    )
    (net (code "150") (name "/USART3_RTS") (class "Default")
      (node (ref "U1") (pin "59") (pinfunction "USART3_RTS_59") (pintype "passive"))
      (node (ref "U6") (pin "6") (pinfunction "A5_6") (pintype "passive"))
    )
    (net (code "151") (name "/USART3_RX") (class "Default")
      (node (ref "U1") (pin "56") (pinfunction "USART3_RX_56") (pintype "passive"))
      (node (ref "U6") (pin "8") (pinfunction "A7_8") (pintype "passive"))
    )
    (net (code "152") (name "/USART3_TX") (class "Default")
      (node (ref "U1") (pin "55") (pinfunction "USART3_TX_55") (pintype "passive"))
      (node (ref "U6") (pin "9") (pinfunction "A8_9") (pintype "passive"))
    )
    (net (code "153") (name "/USART4_RX") (class "Default")
      (node (ref "U1") (pin "24") (pinfunction "UART4_RX_24") (pintype "passive"))
      (node (ref "U7") (pin "3") (pinfunction "A2_3") (pintype "passive"))
    )
    (net (code "154") (name "/USART4_TX") (class "Default")
      (node (ref "U1") (pin "23") (pinfunction "UART4_TX_23") (pintype "passive"))
      (node (ref "U7") (pin "1") (pinfunction "A1_1") (pintype "passive"))
    )
    (net (code "155") (name "/USART7_RX") (class "Default")
      (node (ref "U1") (pin "38") (pinfunction "USART7_RX_38") (pintype "passive"))
      (node (ref "U7") (pin "9") (pinfunction "A8_9") (pintype "passive"))
    )
    (net (code "156") (name "/USART7_TX") (class "Default")
      (node (ref "U1") (pin "39") (pinfunction "USART7_TX_39") (pintype "passive"))
      (node (ref "U7") (pin "8") (pinfunction "A7_8") (pintype "passive"))
    )
    (net (code "157") (name "/USART8_RX") (class "Default")
      (node (ref "U1") (pin "97") (pinfunction "USART8_RX_97") (pintype "passive"))
      (node (ref "U7") (pin "4") (pinfunction "A3_4") (pintype "passive"))
    )
    (net (code "158") (name "/USART8_TX") (class "Default")
      (node (ref "U1") (pin "98") (pinfunction "USART8_TX_98") (pintype "passive"))
      (node (ref "U7") (pin "5") (pinfunction "A4_5") (pintype "passive"))
    )
    (net (code "159") (name "/VBUS_G") (class "Default")
      (node (ref "U13") (pin "2") (pinfunction "G1_2") (pintype "passive"))
      (node (ref "U13") (pin "4") (pinfunction "G2_4") (pintype "passive"))
      (node (ref "u8") (pin "13") (pinfunction "G3_13") (pintype "passive"))
    )
    (net (code "160") (name "/VBUS_VAILD") (class "Default")
      (node (ref "R40") (pin "2") (pinfunction "2_2") (pintype "passive"))
      (node (ref "U1") (pin "15") (pinfunction "VBUS_VAILD_15") (pintype "passive"))
      (node (ref "u8") (pin "9") (pinfunction "VALID3_9") (pintype "passive"))
    )
    (net (code "161") (name "/VBUS_VS") (class "Default")
      (node (ref "C34") (pin "1") (pinfunction "1_1") (pintype "passive"))
      (node (ref "U13") (pin "1") (pinfunction "SI_1") (pintype "passive"))
      (node (ref "U13") (pin "3") (pinfunction "S2_3") (pintype "passive"))
      (node (ref "u8") (pin "14") (pinfunction "VS3_14") (pintype "passive"))
    )
    (net (code "162") (name "/VCAP_1") (class "Default")
      (node (ref "C25") (pin "2") (pinfunction "2_2") (pintype "passive"))
      (node (ref "U1") (pin "49") (pinfunction "VCAP_1_49") (pintype "passive"))
    )
    (net (code "163") (name "/VCAP_2") (class "Default")
      (node (ref "C26") (pin "2") (pinfunction "2_2") (pintype "passive"))
      (node (ref "U1") (pin "73") (pinfunction "VCAP_2_73") (pintype "passive"))
    )
    (net (code "164") (name "/VDD_5V_SENS") (class "Default")
      (node (ref "C59") (pin "2") (pinfunction "2_2") (pintype "passive"))
      (node (ref "R21") (pin "1") (pinfunction "1_1") (pintype "passive"))
      (node (ref "R22") (pin "2") (pinfunction "2_2") (pintype "passive"))
      (node (ref "U1") (pin "29") (pinfunction "VDD_5V_SENS_29") (pintype "passive"))
    )
    (net (code "165") (name "/VDD_G") (class "Default")
      (node (ref "U11") (pin "2") (pinfunction "G1_2") (pintype "passive"))
      (node (ref "U11") (pin "4") (pinfunction "G2_4") (pintype "passive"))
      (node (ref "u8") (pin "17") (pinfunction "G1_17") (pintype "passive"))
    )
    (net (code "166") (name "/VDD_SERVO_SENS") (class "Default")
      (node (ref "R27") (pin "2") (pinfunction "2_2") (pintype "passive"))
      (node (ref "R28") (pin "2") (pinfunction "2_2") (pintype "passive"))
      (node (ref "U2") (pin "14") (pinfunction "VDD_SERVO_SENS_14") (pintype "passive"))
    )
    (net (code "167") (name "/VDD_VS") (class "Default")
      (node (ref "C3") (pin "1") (pinfunction "1_1") (pintype "passive"))
      (node (ref "U11") (pin "1") (pinfunction "SI_1") (pintype "passive"))
      (node (ref "U11") (pin "3") (pinfunction "S2_3") (pintype "passive"))
      (node (ref "u8") (pin "18") (pinfunction "VS1_18") (pintype "passive"))
    )
    (net (code "168") (name "3.3V-2") (class "Default")
      (node (ref "F3") (pin "1") (pinfunction "1_1") (pintype "passive"))
      (node (ref "LDO1") (pin "7") (pinfunction "VOUT2_7") (pintype "passive"))
    )
    (net (code "169") (name "3.3V-4") (class "Default")
      (node (ref "C43") (pin "1") (pinfunction "1_1") (pintype "passive"))
      (node (ref "C46") (pin "1") (pinfunction "1_1") (pintype "passive"))
      (node (ref "C47") (pin "1") (pinfunction "1_1") (pintype "passive"))
      (node (ref "C50") (pin "1") (pinfunction "1_1") (pintype "passive"))
      (node (ref "C53") (pin "1") (pinfunction "1_1") (pintype "passive"))
      (node (ref "C7") (pin "1") (pinfunction "1_1") (pintype "passive"))
      (node (ref "LDO2") (pin "7") (pinfunction "VOUT2_7") (pintype "passive"))
      (node (ref "R61") (pin "2") (pinfunction "2_2") (pintype "passive"))
      (node (ref "U17") (pin "13") (pinfunction "VDDIO_13") (pintype "passive"))
      (node (ref "U17") (pin "2") (pinfunction "VDD_2") (pintype "passive"))
      (node (ref "U18") (pin "1") (pinfunction "VCC_1") (pintype "passive"))
      (node (ref "U9") (pin "1") (pinfunction "NC_1") (pintype "passive"))
      (node (ref "U9") (pin "13") (pinfunction "VDD_13") (pintype "passive"))
      (node (ref "U9") (pin "8") (pinfunction "VDDIO_8") (pintype "passive"))
    )
    (net (code "170") (name "GND") (class "Default")
      (node (ref "3") (pin "8") (pinfunction "R1_8") (pintype "passive"))
      (node (ref "BAT1") (pin "1") (pinfunction "VDD_1") (pintype "passive"))
      (node (ref "C1") (pin "2") (pinfunction "2_2") (pintype "passive"))
      (node (ref "C10") (pin "1") (pinfunction "1_1") (pintype "passive"))
      (node (ref "C11") (pin "C") (pinfunction "2_C") (pintype "passive"))
      (node (ref "C12") (pin "C") (pinfunction "2_C") (pintype "passive"))
      (node (ref "C13") (pin "C") (pinfunction "2_C") (pintype "passive"))
      (node (ref "C14") (pin "1") (pinfunction "1_1") (pintype "passive"))
      (node (ref "C15") (pin "1") (pinfunction "1_1") (pintype "passive"))
      (node (ref "C16") (pin "1") (pinfunction "1_1") (pintype "passive"))
      (node (ref "C17") (pin "1") (pinfunction "1_1") (pintype "passive"))
      (node (ref "C18") (pin "1") (pinfunction "1_1") (pintype "passive"))
      (node (ref "C19") (pin "1") (pinfunction "1_1") (pintype "passive"))
      (node (ref "C2") (pin "2") (pinfunction "2_2") (pintype "passive"))
      (node (ref "C20") (pin "1") (pinfunction "1_1") (pintype "passive"))
      (node (ref "C21") (pin "1") (pinfunction "1_1") (pintype "passive"))
      (node (ref "C22") (pin "1") (pinfunction "1_1") (pintype "passive"))
      (node (ref "C23") (pin "2") (pinfunction "2_2") (pintype "passive"))
      (node (ref "C24") (pin "1") (pinfunction "1_1") (pintype "passive"))
      (node (ref "C25") (pin "1") (pinfunction "1_1") (pintype "passive"))
      (node (ref "C26") (pin "1") (pinfunction "1_1") (pintype "passive"))
      (node (ref "C27") (pin "1") (pinfunction "1_1") (pintype "passive"))
      (node (ref "C28") (pin "1") (pinfunction "1_1") (pintype "passive"))
      (node (ref "C29") (pin "1") (pinfunction "1_1") (pintype "passive"))
      (node (ref "C3") (pin "2") (pinfunction "2_2") (pintype "passive"))
      (node (ref "C30") (pin "1") (pinfunction "1_1") (pintype "passive"))
      (node (ref "C31") (pin "1") (pinfunction "1_1") (pintype "passive"))
      (node (ref "C32") (pin "2") (pinfunction "2_2") (pintype "passive"))
      (node (ref "C33") (pin "2") (pinfunction "2_2") (pintype "passive"))
      (node (ref "C34") (pin "2") (pinfunction "2_2") (pintype "passive"))
      (node (ref "C35") (pin "1") (pinfunction "1_1") (pintype "passive"))
      (node (ref "C36") (pin "1") (pinfunction "1_1") (pintype "passive"))
      (node (ref "C37") (pin "1") (pinfunction "1_1") (pintype "passive"))
      (node (ref "C38") (pin "1") (pinfunction "1_1") (pintype "passive"))
      (node (ref "C39") (pin "1") (pinfunction "1_1") (pintype "passive"))
      (node (ref "C4") (pin "2") (pinfunction "2_2") (pintype "passive"))
      (node (ref "C40") (pin "1") (pinfunction "1_1") (pintype "passive"))
      (node (ref "C41") (pin "1") (pinfunction "1_1") (pintype "passive"))
      (node (ref "C42") (pin "1") (pinfunction "1_1") (pintype "passive"))
      (node (ref "C43") (pin "2") (pinfunction "2_2") (pintype "passive"))
      (node (ref "C44") (pin "2") (pinfunction "2_2") (pintype "passive"))
      (node (ref "C45") (pin "2") (pinfunction "2_2") (pintype "passive"))
      (node (ref "C46") (pin "2") (pinfunction "2_2") (pintype "passive"))
      (node (ref "C47") (pin "2") (pinfunction "2_2") (pintype "passive"))
      (node (ref "C48") (pin "1") (pinfunction "1_1") (pintype "passive"))
      (node (ref "C49") (pin "1") (pinfunction "1_1") (pintype "passive"))
      (node (ref "C5") (pin "1") (pinfunction "1_1") (pintype "passive"))
      (node (ref "C50") (pin "2") (pinfunction "2_2") (pintype "passive"))
      (node (ref "C52") (pin "2") (pinfunction "2_2") (pintype "passive"))
      (node (ref "C53") (pin "2") (pinfunction "2_2") (pintype "passive"))
      (node (ref "C54") (pin "2") (pinfunction "2_2") (pintype "passive"))
      (node (ref "C55") (pin "2") (pinfunction "2_2") (pintype "passive"))
      (node (ref "C56") (pin "1") (pinfunction "1_1") (pintype "passive"))
      (node (ref "C57") (pin "1") (pinfunction "1_1") (pintype "passive"))
      (node (ref "C58") (pin "1") (pinfunction "1_1") (pintype "passive"))
      (node (ref "C59") (pin "1") (pinfunction "1_1") (pintype "passive"))
      (node (ref "C6") (pin "1") (pinfunction "1_1") (pintype "passive"))
      (node (ref "C60") (pin "1") (pinfunction "1_1") (pintype "passive"))
      (node (ref "C61") (pin "1") (pinfunction "1_1") (pintype "passive"))
      (node (ref "C62") (pin "1") (pinfunction "1_1") (pintype "passive"))
      (node (ref "C7") (pin "2") (pinfunction "2_2") (pintype "passive"))
      (node (ref "C8") (pin "1") (pinfunction "1_1") (pintype "passive"))
      (node (ref "C9") (pin "1") (pinfunction "1_1") (pintype "passive"))
      (node (ref "CON2") (pin "6") (pinfunction "GND_6") (pintype "passive"))
      (node (ref "CON2") (pin "NC") (pinfunction "NC_NC") (pintype "passive"))
      (node (ref "CON3") (pin "10") (pinfunction "9_10") (pintype "passive"))
      (node (ref "CON3") (pin "2") (pinfunction "1_2") (pintype "passive"))
      (node (ref "CON3") (pin "9") (pinfunction "8_9") (pintype "passive"))
      (node (ref "D2") (pin "1") (pinfunction "A_1") (pintype "passive"))
      (node (ref "D3") (pin "1") (pinfunction "A_1") (pintype "passive"))
      (node (ref "ESD2") (pin "2") (pinfunction "2_2") (pintype "passive"))
      (node (ref "F3") (pin "0") (pinfunction "0_0") (pintype "passive"))
      (node (ref "IO1") (pin "18") (pintype "passive"))
      (node (ref "IO2") (pin "15") (pintype "passive"))
      (node (ref "IO2") (pin "18") (pintype "passive"))
      (node (ref "IO2") (pin "21") (pinfunction "21_21") (pintype "passive"))
      (node (ref "KEY1") (pin "A2") (pinfunction "2_A2") (pintype "passive"))
      (node (ref "KEY2") (pin "A2") (pinfunction "2_A2") (pintype "passive"))
      (node (ref "LDO1") (pin "2") (pinfunction "GND_2") (pintype "passive"))
      (node (ref "LDO2") (pin "2") (pinfunction "GND_2") (pintype "passive"))
      (node (ref "LDO2") (pin "6") (pinfunction "NC_6") (pintype "passive"))
      (node (ref "R12") (pin "1") (pinfunction "1_1") (pintype "passive"))
      (node (ref "R14") (pin "1") (pinfunction "1_1") (pintype "passive"))
      (node (ref "R15") (pin "2") (pinfunction "2_2") (pintype "passive"))
      (node (ref "R16") (pin "2") (pinfunction "2_2") (pintype "passive"))
      (node (ref "R18") (pin "1") (pinfunction "1_1") (pintype "passive"))
      (node (ref "R19") (pin "1") (pinfunction "1_1") (pintype "passive"))
      (node (ref "R20") (pin "2") (pinfunction "2_2") (pintype "passive"))
      (node (ref "R22") (pin "1") (pinfunction "1_1") (pintype "passive"))
      (node (ref "R24") (pin "1") (pinfunction "1_1") (pintype "passive"))
      (node (ref "R28") (pin "1") (pinfunction "1_1") (pintype "passive"))
      (node (ref "R33") (pin "2") (pinfunction "2_2") (pintype "passive"))
      (node (ref "R36") (pin "1") (pinfunction "1_1") (pintype "passive"))
      (node (ref "R37") (pin "1") (pinfunction "1_1") (pintype "passive"))
      (node (ref "R42") (pin "1") (pinfunction "1_1") (pintype "passive"))
      (node (ref "R44") (pin "1") (pinfunction "1_1") (pintype "passive"))
      (node (ref "R61") (pin "1") (pinfunction "1_1") (pintype "passive"))
      (node (ref "R8") (pin "1") (pinfunction "1_1") (pintype "passive"))
      (node (ref "R9") (pin "1") (pinfunction "1_1") (pintype "passive"))
      (node (ref "U1") (pin "10") (pinfunction "GND_10") (pintype "passive"))
      (node (ref "U1") (pin "20") (pinfunction "GND_20") (pintype "passive"))
      (node (ref "U1") (pin "27") (pinfunction "GND_27") (pintype "passive"))
      (node (ref "U1") (pin "74") (pinfunction "GND_74") (pintype "passive"))
      (node (ref "U1") (pin "99") (pinfunction "GND_99") (pintype "passive"))
      (node (ref "U14") (pin "2") (pinfunction "GND_2") (pintype "passive"))
      (node (ref "U15") (pin "5") (pinfunction "GND_5") (pintype "passive"))
      (node (ref "U16") (pin "2") (pinfunction "VSS_2") (pintype "passive"))
      (node (ref "U16") (pin "6") (pinfunction "VBAT_6") (pintype "passive"))
      (node (ref "U17") (pin "11") (pinfunction "GND_11") (pintype "passive"))
      (node (ref "U17") (pin "6") (pinfunction "I2C/SPI_6") (pintype "passive"))
      (node (ref "U17") (pin "9") (pinfunction "SOC_9") (pintype "passive"))
      (node (ref "U18") (pin "2") (pinfunction "GND_2") (pintype "passive"))
      (node (ref "U18") (pin "3") (pinfunction "GND_3") (pintype "passive"))
      (node (ref "U19") (pin "2") (pinfunction "VSS_2") (pintype "passive"))
      (node (ref "U19") (pin "6") (pinfunction "VBAT_6") (pintype "passive"))
      (node (ref "U2") (pin "23") (pinfunction "GND_23") (pintype "passive"))
      (node (ref "U2") (pin "35") (pinfunction "GND_35") (pintype "passive"))
      (node (ref "U2") (pin "47") (pinfunction "GND_47") (pintype "passive"))
      (node (ref "U2") (pin "8") (pinfunction "GND_8") (pintype "passive"))
      (node (ref "U20") (pin "11") (pinfunction "GND_11") (pintype "passive"))
      (node (ref "U20") (pin "12") (pinfunction "GND_12") (pintype "passive"))
      (node (ref "U20") (pin "13") (pinfunction "GND_13") (pintype "passive"))
      (node (ref "U20") (pin "22") (pinfunction "OE_22") (pintype "passive"))
      (node (ref "U3") (pin "11") (pinfunction "GND_11") (pintype "passive"))
      (node (ref "U3") (pin "12") (pinfunction "GND_12") (pintype "passive"))
      (node (ref "U3") (pin "13") (pinfunction "GND_13") (pintype "passive"))
      (node (ref "U3") (pin "22") (pinfunction "OE_22") (pintype "passive"))
      (node (ref "U4") (pin "1") (pinfunction "1OE_1") (pintype "passive"))
      (node (ref "U4") (pin "4") (pinfunction "GND_4") (pintype "passive"))
      (node (ref "U5") (pin "4") (pinfunction "GND_4") (pintype "passive"))
      (node (ref "U6") (pin "11") (pinfunction "GND_11") (pintype "passive"))
      (node (ref "U7") (pin "11") (pinfunction "GND_11") (pintype "passive"))
      (node (ref "U9") (pin "11") (pinfunction "FSYNC_11") (pintype "passive"))
      (node (ref "U9") (pin "18") (pinfunction "GND_18") (pintype "passive"))
      (node (ref "U9") (pin "20") (pinfunction "RES_20") (pintype "passive"))
      (node (ref "USB") (pin "5") (pinfunction "GND_5") (pintype "passive"))
      (node (ref "Y1") (pin "2") (pinfunction "G_2") (pintype "passive"))
      (node (ref "Y1") (pin "4") (pinfunction "G_4") (pintype "passive"))
      (node (ref "Y2") (pin "2") (pinfunction "G_2") (pintype "passive"))
      (node (ref "Y2") (pin "4") (pinfunction "G_4") (pintype "passive"))
      (node (ref "u8") (pin "10") (pinfunction "GND_10") (pintype "passive"))
      (node (ref "u8") (pin "24") (pinfunction "HYS_24") (pintype "passive"))
    )
    (net (code "171") (name "IO-3V3") (class "Default")
      (node (ref "C10") (pin "2") (pinfunction "2_2") (pintype "passive"))
      (node (ref "C39") (pin "2") (pinfunction "2_2") (pintype "passive"))
      (node (ref "C41") (pin "2") (pinfunction "2_2") (pintype "passive"))
      (node (ref "C48") (pin "2") (pinfunction "2_2") (pintype "passive"))
      (node (ref "C54") (pin "1") (pinfunction "1_1") (pintype "passive"))
      (node (ref "C55") (pin "1") (pinfunction "1_1") (pintype "passive"))
      (node (ref "C58") (pin "2") (pinfunction "2_2") (pintype "passive"))
      (node (ref "C60") (pin "2") (pinfunction "2_2") (pintype "passive"))
      (node (ref "C62") (pin "2") (pinfunction "2_2") (pintype "passive"))
      (node (ref "LDO2") (pin "8") (pinfunction "VOUT1_8") (pintype "passive"))
      (node (ref "R46") (pin "1") (pinfunction "1_1") (pintype "passive"))
      (node (ref "R7") (pin "2") (pinfunction "2_2") (pintype "passive"))
      (node (ref "U2") (pin "24") (pinfunction "3V3_24") (pintype "passive"))
      (node (ref "U2") (pin "36") (pinfunction "3V3_36") (pintype "passive"))
      (node (ref "U2") (pin "48") (pinfunction "3V3_48") (pintype "passive"))
      (node (ref "U2") (pin "9") (pinfunction "3V3_9") (pintype "passive"))
      (node (ref "U20") (pin "1") (pinfunction "VCCA_1") (pintype "passive"))
      (node (ref "U20") (pin "2") (pinfunction "DIR_2") (pintype "passive"))
      (node (ref "U20") (pin "23") (pinfunction "VCCB_23") (pintype "passive"))
      (node (ref "U20") (pin "24") (pinfunction "VCCB_24") (pintype "passive"))
      (node (ref "U3") (pin "1") (pinfunction "VCCA_1") (pintype "passive"))
      (node (ref "U3") (pin "2") (pinfunction "DIR_2") (pintype "passive"))
      (node (ref "U3") (pin "23") (pinfunction "VCCB_23") (pintype "passive"))
      (node (ref "U3") (pin "24") (pinfunction "VCCB_24") (pintype "passive"))
      (node (ref "U4") (pin "8") (pinfunction "VCC_8") (pintype "passive"))
      (node (ref "d5") (pin "1") (pinfunction "A_1") (pintype "passive"))
    )
    (net (code "172") (name "MCU_3V3") (class "Default")
      (node (ref "3") (pin "1") (pinfunction "R1_1") (pintype "passive"))
      (node (ref "3") (pin "2") (pinfunction "R2_2") (pintype "passive"))
      (node (ref "3") (pin "3") (pinfunction "R3_3") (pintype "passive"))
      (node (ref "3") (pin "4") (pinfunction "R4_4") (pintype "passive"))
      (node (ref "C14") (pin "2") (pinfunction "2_2") (pintype "passive"))
      (node (ref "C15") (pin "2") (pinfunction "2_2") (pintype "passive"))
      (node (ref "C36") (pin "2") (pinfunction "2_2") (pintype "passive"))
      (node (ref "C37") (pin "2") (pinfunction "2_2") (pintype "passive"))
      (node (ref "C38") (pin "2") (pinfunction "2_2") (pintype "passive"))
      (node (ref "C42") (pin "2") (pinfunction "2_2") (pintype "passive"))
      (node (ref "C49") (pin "2") (pinfunction "2_2") (pintype "passive"))
      (node (ref "C6") (pin "2") (pinfunction "2_2") (pintype "passive"))
      (node (ref "C9") (pin "2") (pinfunction "2_2") (pintype "passive"))
      (node (ref "LDO1") (pin "8") (pinfunction "VOUT1_8") (pintype "passive"))
      (node (ref "R10") (pin "1") (pinfunction "1_1") (pintype "passive"))
      (node (ref "R17") (pin "1") (pinfunction "1_1") (pintype "passive"))
      (node (ref "R25") (pin "1") (pinfunction "1_1") (pintype "passive"))
      (node (ref "R29") (pin "1") (pinfunction "1_1") (pintype "passive"))
      (node (ref "R30") (pin "1") (pinfunction "1_1") (pintype "passive"))
      (node (ref "R31") (pin "1") (pinfunction "1_1") (pintype "passive"))
      (node (ref "R34") (pin "2") (pinfunction "2_2") (pintype "passive"))
      (node (ref "U1") (pin "100") (pinfunction "VCC_100") (pintype "passive"))
      (node (ref "U1") (pin "11") (pinfunction "VCC_11") (pintype "passive"))
      (node (ref "U1") (pin "19") (pinfunction "VCC_19") (pintype "passive"))
      (node (ref "U1") (pin "21") (pinfunction "VCC_21") (pintype "passive"))
      (node (ref "U1") (pin "22") (pinfunction "VCC_22") (pintype "passive"))
      (node (ref "U1") (pin "28") (pinfunction "VCC_28") (pintype "passive"))
      (node (ref "U1") (pin "50") (pinfunction "VCC_50") (pintype "passive"))
      (node (ref "U1") (pin "75") (pinfunction "VCC_75") (pintype "passive"))
      (node (ref "U6") (pin "10") (pinfunction "OE_10") (pintype "passive"))
      (node (ref "U6") (pin "19") (pinfunction "VCCB_19") (pintype "passive"))
      (node (ref "U6") (pin "2") (pinfunction "VCCA_2") (pintype "passive"))
      (node (ref "U7") (pin "10") (pinfunction "OE_10") (pintype "passive"))
      (node (ref "U7") (pin "19") (pinfunction "VCCB_19") (pintype "passive"))
      (node (ref "U7") (pin "2") (pinfunction "VCCA_2") (pintype "passive"))
    )
    (net (code "173") (name "Net-(D4-LED1)") (class "Default")
      (node (ref "D4") (pin "C1") (pinfunction "LED1_C1") (pintype "passive"))
      (node (ref "U15") (pin "9") (pinfunction "OUT20_9") (pintype "passive"))
    )
    (net (code "174") (name "Net-(D4-LED2)") (class "Default")
      (node (ref "D4") (pin "C2") (pinfunction "LED2_C2") (pintype "passive"))
      (node (ref "U15") (pin "8") (pinfunction "OUT1_8") (pintype "passive"))
    )
    (net (code "175") (name "Net-(D4-LED3)") (class "Default")
      (node (ref "D4") (pin "C3") (pinfunction "LED3_C3") (pintype "passive"))
      (node (ref "U15") (pin "7") (pinfunction "OUT2_7") (pintype "passive"))
    )
    (net (code "176") (name "Net-(LDO1-BYP)") (class "Default")
      (node (ref "C45") (pin "1") (pinfunction "1_1") (pintype "passive"))
      (node (ref "LDO1") (pin "3") (pinfunction "BYP_3") (pintype "passive"))
    )
    (net (code "177") (name "Net-(LDO2-BYP)") (class "Default")
      (node (ref "C44") (pin "1") (pinfunction "1_1") (pintype "passive"))
      (node (ref "LDO2") (pin "3") (pinfunction "BYP_3") (pintype "passive"))
    )
    (net (code "178") (name "Net-(LED1-BLUE)") (class "Default")
      (node (ref "LED1") (pin "2") (pinfunction "BLUE_2") (pintype "passive"))
      (node (ref "R48") (pin "1") (pinfunction "1_1") (pintype "passive"))
    )
    (net (code "179") (name "Net-(LED1-GR)") (class "Default")
      (node (ref "LED1") (pin "1") (pinfunction "GR_1") (pintype "passive"))
      (node (ref "R47") (pin "1") (pinfunction "1_1") (pintype "passive"))
    )
    (net (code "180") (name "Net-(LED1-REG)") (class "Default")
      (node (ref "LED1") (pin "4") (pinfunction "REG_4") (pintype "passive"))
      (node (ref "R41") (pin "1") (pinfunction "1_1") (pintype "passive"))
    )
    (net (code "181") (name "Net-(R11-Pad2)") (class "Default")
      (node (ref "R11") (pin "2") (pinfunction "2_2") (pintype "passive"))
      (node (ref "R54") (pin "1") (pinfunction "1_1") (pintype "passive"))
      (node (ref "R55") (pin "2") (pinfunction "2_2") (pintype "passive"))
    )
    (net (code "182") (name "Net-(U2-SERVO_IN_FAULT)") (class "Default")
      (node (ref "R46") (pin "2") (pinfunction "2_2") (pintype "passive"))
      (node (ref "U2") (pin "38") (pinfunction "SERVO_IN_FAULT_38") (pintype "passive"))
    )
    (net (code "183") (name "Net-(U5-HOLD)") (class "Default")
      (node (ref "R49") (pin "2") (pinfunction "2_2") (pintype "passive"))
      (node (ref "U5") (pin "7") (pinfunction "HOLD_7") (pintype "passive"))
    )
    (net (code "184") (name "Net-(U9-REGOUT)") (class "Default")
      (node (ref "C35") (pin "2") (pinfunction "2_2") (pintype "passive"))
      (node (ref "U9") (pin "10") (pinfunction "REGOUT_10") (pintype "passive"))
    )
    (net (code "185") (name "Net-(U15-RESET)") (class "Default")
      (node (ref "R13") (pin "2") (pinfunction "2_2") (pintype "passive"))
      (node (ref "U15") (pin "4") (pinfunction "RESET_4") (pintype "passive"))
    )
    (net (code "186") (name "Net-(U15-REXT)") (class "Default")
      (node (ref "R14") (pin "2") (pinfunction "2_2") (pintype "passive"))
      (node (ref "U15") (pin "6") (pinfunction "REXT_6") (pintype "passive"))
    )
    (net (code "187") (name "Net-(U16-CE)") (class "Default")
      (node (ref "R15") (pin "1") (pinfunction "1_1") (pintype "passive"))
      (node (ref "U16") (pin "5") (pinfunction "CE_5") (pintype "passive"))
      (node (ref "U19") (pin "5") (pinfunction "CE_5") (pintype "passive"))
    )
    (net (code "188") (name "Net-(U16-ILIM)") (class "Default")
      (node (ref "R9") (pin "2") (pinfunction "2_2") (pintype "passive"))
      (node (ref "U16") (pin "7") (pinfunction "ILIM_7") (pintype "passive"))
    )
    (net (code "189") (name "Net-(U17-C1)") (class "Default")
      (node (ref "C52") (pin "1") (pinfunction "1_1") (pintype "passive"))
      (node (ref "U17") (pin "10") (pinfunction "C1_10") (pintype "passive"))
    )
    (net (code "190") (name "Net-(U17-SETC)") (class "Default")
      (node (ref "C51") (pin "1") (pinfunction "1_1") (pintype "passive"))
      (node (ref "U17") (pin "12") (pinfunction "SETC_12") (pintype "passive"))
    )
    (net (code "191") (name "Net-(U17-SETP)") (class "Default")
      (node (ref "C51") (pin "2") (pinfunction "2_2") (pintype "passive"))
      (node (ref "U17") (pin "8") (pinfunction "SETP_8") (pintype "passive"))
    )
    (net (code "192") (name "Net-(U19-ILIM)") (class "Default")
      (node (ref "R16") (pin "1") (pinfunction "1_1") (pintype "passive"))
      (node (ref "U19") (pin "7") (pinfunction "ILIM_7") (pintype "passive"))
    )
    (net (code "193") (name "Net-(d5-K)") (class "Default")
      (node (ref "R45") (pin "1") (pinfunction "1_1") (pintype "passive"))
      (node (ref "d5") (pin "2") (pinfunction "K_2") (pintype "passive"))
    )
    (net (code "194") (name "Net-(u8-OV1)") (class "Default")
      (node (ref "C1") (pin "1") (pinfunction "1_1") (pintype "passive"))
      (node (ref "R18") (pin "2") (pinfunction "2_2") (pintype "passive"))
      (node (ref "R4") (pin "1") (pinfunction "1_1") (pintype "passive"))
      (node (ref "u8") (pin "2") (pinfunction "OV1_2") (pintype "passive"))
    )
    (net (code "195") (name "Net-(u8-OV2)") (class "Default")
      (node (ref "C2") (pin "1") (pinfunction "1_1") (pintype "passive"))
      (node (ref "R3") (pin "1") (pinfunction "1_1") (pintype "passive"))
      (node (ref "R8") (pin "2") (pinfunction "2_2") (pintype "passive"))
      (node (ref "u8") (pin "4") (pinfunction "OV2_4") (pintype "passive"))
    )
    (net (code "196") (name "Net-(u8-OV3)") (class "Default")
      (node (ref "R19") (pin "2") (pinfunction "2_2") (pintype "passive"))
      (node (ref "R6") (pin "1") (pinfunction "1_1") (pintype "passive"))
      (node (ref "u8") (pin "6") (pinfunction "OV3_6") (pintype "passive"))
    )
    (net (code "197") (name "Net-(u8-UV1)") (class "Default")
      (node (ref "R2") (pin "1") (pinfunction "1_1") (pintype "passive"))
      (node (ref "R4") (pin "2") (pinfunction "2_2") (pintype "passive"))
      (node (ref "u8") (pin "1") (pinfunction "UV1_1") (pintype "passive"))
    )
    (net (code "198") (name "Net-(u8-UV2)") (class "Default")
      (node (ref "R1") (pin "1") (pinfunction "1_1") (pintype "passive"))
      (node (ref "R3") (pin "2") (pinfunction "2_2") (pintype "passive"))
      (node (ref "u8") (pin "3") (pinfunction "UV2_3") (pintype "passive"))
    )
    (net (code "199") (name "Net-(u8-UV3)") (class "Default")
      (node (ref "C33") (pin "1") (pinfunction "1_1") (pintype "passive"))
      (node (ref "R5") (pin "1") (pinfunction "1_1") (pintype "passive"))
      (node (ref "R6") (pin "2") (pinfunction "2_2") (pintype "passive"))
      (node (ref "u8") (pin "5") (pinfunction "UV3_5") (pintype "passive"))
    )
    (net (code "200") (name "RC_IN") (class "Default")
      (node (ref "ESD2") (pin "1") (pinfunction "1_1") (pintype "passive"))
      (node (ref "R50") (pin "2") (pinfunction "2_2") (pintype "passive"))
      (node (ref "R53") (pin "1") (pinfunction "1_1") (pintype "passive"))
      (node (ref "U4") (pin "2") (pinfunction "1A_2") (pintype "passive"))
    )
    (net (code "201") (name "RC_IN_PORT") (class "Default")
      (node (ref "IO1") (pin "2") (pintype "passive"))
      (node (ref "R50") (pin "1") (pinfunction "1_1") (pintype "passive"))
    )
    (net (code "202") (name "RSSI_IN_PROT") (class "Default")
      (node (ref "IO1") (pin "3") (pintype "passive"))
      (node (ref "R54") (pin "2") (pinfunction "2_2") (pintype "passive"))
    )
    (net (code "203") (name "TF_VCC") (class "Default")
      (node (ref "C16") (pin "2") (pinfunction "2_2") (pintype "passive"))
      (node (ref "C20") (pin "2") (pinfunction "2_2") (pintype "passive"))
      (node (ref "CON2") (pin "4") (pinfunction "3V3_4") (pintype "passive"))
      (node (ref "F3") (pin "2") (pinfunction "2_2") (pintype "passive"))
      (node (ref "R49") (pin "1") (pinfunction "1_1") (pintype "passive"))
      (node (ref "U5") (pin "3") (pinfunction "WP_3") (pintype "passive"))
      (node (ref "U5") (pin "8") (pinfunction "3V3_8") (pintype "passive"))
    )
    (net (code "204") (name "VBAT") (class "Default")
      (node (ref "BAT1") (pin "2") (pinfunction "GND_2") (pintype "passive"))
      (node (ref "R45") (pin "2") (pinfunction "2_2") (pintype "passive"))
      (node (ref "U1") (pin "6") (pinfunction "VBAT_6") (pintype "passive"))
      (node (ref "U2") (pin "1") (pinfunction "VBAT_1") (pintype "passive"))
    )
    (net (code "205") (name "VBUS") (class "Default")
      (node (ref "C22") (pin "2") (pinfunction "2_2") (pintype "passive"))
      (node (ref "C30") (pin "2") (pinfunction "2_2") (pintype "passive"))
      (node (ref "C31") (pin "2") (pinfunction "2_2") (pintype "passive"))
      (node (ref "IO2") (pin "17") (pintype "passive"))
      (node (ref "R5") (pin "2") (pinfunction "2_2") (pintype "passive"))
      (node (ref "U1") (pin "68") (pinfunction "VBUS_68") (pintype "passive"))
      (node (ref "U13") (pin "7") (pinfunction "D1_7") (pintype "passive"))
      (node (ref "U13") (pin "8") (pinfunction "D1_8") (pintype "passive"))
      (node (ref "U14") (pin "5") (pinfunction "VBUS_5") (pintype "passive"))
      (node (ref "USB") (pin "1") (pinfunction "VBUS_1") (pintype "passive"))
      (node (ref "u8") (pin "19") (pinfunction "V3_19") (pintype "passive"))
    )
    (net (code "206") (name "VCC_OUT1") (class "Default")
      (node (ref "IO2") (pin "8") (pintype "passive"))
      (node (ref "U16") (pin "8") (pinfunction "OUT_8") (pintype "passive"))
    )
    (net (code "207") (name "VCC_OUT2") (class "Default")
      (node (ref "IO2") (pin "6") (pintype "passive"))
      (node (ref "U19") (pin "8") (pinfunction "OUT_8") (pintype "passive"))
    )
    (net (code "208") (name "VDD_5V_BRICK") (class "Default")
      (node (ref "C11") (pin "A") (pinfunction "1_A") (pintype "passive"))
      (node (ref "C18") (pin "2") (pinfunction "2_2") (pintype "passive"))
      (node (ref "D2") (pin "2") (pinfunction "K_2") (pintype "passive"))
      (node (ref "F2") (pin "2") (pinfunction "2_2") (pintype "passive"))
      (node (ref "R2") (pin "2") (pinfunction "2_2") (pintype "passive"))
      (node (ref "U11") (pin "7") (pinfunction "D1_7") (pintype "passive"))
      (node (ref "U11") (pin "8") (pinfunction "D1_8") (pintype "passive"))
      (node (ref "u8") (pin "21") (pinfunction "V1_21") (pintype "passive"))
    )
    (net (code "209") (name "VDD_5V_BRICK_IN") (class "Default")
      (node (ref "F2") (pin "1") (pinfunction "1_1") (pintype "passive"))
      (node (ref "IO2") (pin "40") (pinfunction "40_40") (pintype "passive"))
      (node (ref "IO2") (pin "41") (pinfunction "41_41") (pintype "passive"))
    )
    (net (code "210") (name "VDD_5V_IN") (class "Default")
      (node (ref "C12") (pin "A") (pinfunction "1_A") (pintype "passive"))
      (node (ref "C17") (pin "2") (pinfunction "2_2") (pintype "passive"))
      (node (ref "C19") (pin "2") (pinfunction "2_2") (pintype "passive"))
      (node (ref "C29") (pin "2") (pinfunction "2_2") (pintype "passive"))
      (node (ref "C40") (pin "2") (pinfunction "2_2") (pintype "passive"))
      (node (ref "C5") (pin "2") (pinfunction "2_2") (pintype "passive"))
      (node (ref "C56") (pin "2") (pinfunction "2_2") (pintype "passive"))
      (node (ref "C57") (pin "2") (pinfunction "2_2") (pintype "passive"))
      (node (ref "CON3") (pin "1") (pinfunction "0_1") (pintype "passive"))
      (node (ref "CON3") (pin "3") (pinfunction "2_3") (pintype "passive"))
      (node (ref "D4") (pin "A1") (pinfunction "VCC_A1") (pintype "passive"))
      (node (ref "D4") (pin "A2") (pinfunction "VCC_A2") (pintype "passive"))
      (node (ref "D4") (pin "A3") (pinfunction "VCC_A3") (pintype "passive"))
      (node (ref "L1") (pin "2") (pinfunction "2_2") (pintype "passive"))
      (node (ref "LDO1") (pin "1") (pinfunction "VIN_1") (pintype "passive"))
      (node (ref "LDO1") (pin "4") (pinfunction "EN2_4") (pintype "passive"))
      (node (ref "LDO1") (pin "5") (pinfunction "EN1_5") (pintype "passive"))
      (node (ref "LDO2") (pin "1") (pinfunction "VIN_1") (pintype "passive"))
      (node (ref "LDO2") (pin "4") (pinfunction "EN2_4") (pintype "passive"))
      (node (ref "LDO2") (pin "5") (pinfunction "EN1_5") (pintype "passive"))
      (node (ref "LED1") (pin "3") (pinfunction "COM_3") (pintype "passive"))
      (node (ref "R13") (pin "1") (pinfunction "1_1") (pintype "passive"))
      (node (ref "R21") (pin "2") (pinfunction "2_2") (pintype "passive"))
      (node (ref "R38") (pin "1") (pinfunction "1_1") (pintype "passive"))
      (node (ref "R39") (pin "1") (pinfunction "1_1") (pintype "passive"))
      (node (ref "R40") (pin "1") (pinfunction "1_1") (pintype "passive"))
      (node (ref "U11") (pin "5") (pinfunction "D2_5") (pintype "passive"))
      (node (ref "U11") (pin "6") (pinfunction "D2_6") (pintype "passive"))
      (node (ref "U12") (pin "5") (pinfunction "D2_5") (pintype "passive"))
      (node (ref "U12") (pin "6") (pinfunction "D2_6") (pintype "passive"))
      (node (ref "U13") (pin "5") (pinfunction "D2_5") (pintype "passive"))
      (node (ref "U13") (pin "6") (pinfunction "D2_6") (pintype "passive"))
      (node (ref "U15") (pin "1") (pinfunction "SHDN_1") (pintype "passive"))
      (node (ref "U15") (pin "10") (pinfunction "VDD_10") (pintype "passive"))
      (node (ref "U16") (pin "1") (pinfunction "IN_1") (pintype "passive"))
      (node (ref "U19") (pin "1") (pinfunction "IN_1") (pintype "passive"))
      (node (ref "u8") (pin "12") (pinfunction "VOUT_12") (pintype "passive"))
    )
    (net (code "211") (name "VDD_RC") (class "Default")
      (node (ref "IO1") (pin "1") (pintype "passive"))
      (node (ref "L1") (pin "1") (pinfunction "1_1") (pintype "passive"))
    )
    (net (code "212") (name "VDD_SERVO") (class "Default")
      (node (ref "C13") (pin "A") (pinfunction "1_A") (pintype "passive"))
      (node (ref "C21") (pin "2") (pinfunction "2_2") (pintype "passive"))
      (node (ref "D3") (pin "2") (pinfunction "K_2") (pintype "passive"))
      (node (ref "F1") (pin "1") (pinfunction "1_1") (pintype "passive"))
      (node (ref "R1") (pin "2") (pinfunction "2_2") (pintype "passive"))
      (node (ref "R27") (pin "1") (pinfunction "1_1") (pintype "passive"))
      (node (ref "U12") (pin "7") (pinfunction "D1_7") (pintype "passive"))
      (node (ref "U12") (pin "8") (pinfunction "D1_8") (pintype "passive"))
      (node (ref "u8") (pin "20") (pinfunction "V2_20") (pintype "passive"))
    )
    (net (code "213") (name "VDD_SERVO_IN") (class "Default")
      (node (ref "F1") (pin "2") (pinfunction "2_2") (pintype "passive"))
      (node (ref "IO1") (pin "17") (pintype "passive"))
    )
    (net (code "214") (name "unconnected-(CON3-19-Pad20)") (class "Default")
      (node (ref "CON3") (pin "20") (pinfunction "19_20") (pintype "passive"))
    )
    (net (code "215") (name "unconnected-(IO2-Pad22)") (class "Default")
      (node (ref "IO2") (pin "22") (pinfunction "22_22") (pintype "passive"))
    )
    (net (code "216") (name "unconnected-(IO2-Pad23)") (class "Default")
      (node (ref "IO2") (pin "23") (pinfunction "23_23") (pintype "passive"))
    )
    (net (code "217") (name "unconnected-(KEY1-1-PadA1)") (class "Default")
      (node (ref "KEY1") (pin "A1") (pinfunction "1_A1") (pintype "passive"))
    )
    (net (code "218") (name "unconnected-(KEY1-3-PadA3)") (class "Default")
      (node (ref "KEY1") (pin "A3") (pinfunction "3_A3") (pintype "passive"))
    )
    (net (code "219") (name "unconnected-(KEY2-1-PadA1)") (class "Default")
      (node (ref "KEY2") (pin "A1") (pinfunction "1_A1") (pintype "passive"))
    )
    (net (code "220") (name "unconnected-(KEY2-3-PadA3)") (class "Default")
      (node (ref "KEY2") (pin "A3") (pinfunction "3_A3") (pintype "passive"))
    )
    (net (code "221") (name "unconnected-(LDO1-NC-Pad6)") (class "Default")
      (node (ref "LDO1") (pin "6") (pinfunction "NC_6") (pintype "passive"))
    )
    (net (code "222") (name "unconnected-(U2-NC-Pad3)") (class "Default")
      (node (ref "U2") (pin "3") (pinfunction "NC_3") (pintype "passive"))
    )
    (net (code "223") (name "unconnected-(U2-NC-Pad4)") (class "Default")
      (node (ref "U2") (pin "4") (pinfunction "NC_4") (pintype "passive"))
    )
    (net (code "224") (name "unconnected-(U2-NC-Pad25)") (class "Default")
      (node (ref "U2") (pin "25") (pinfunction "NC_25") (pintype "passive"))
    )
    (net (code "225") (name "unconnected-(U2-NC-Pad32)") (class "Default")
      (node (ref "U2") (pin "32") (pinfunction "NC_32") (pintype "passive"))
    )
    (net (code "226") (name "unconnected-(U2-NC-Pad42)") (class "Default")
      (node (ref "U2") (pin "42") (pinfunction "NC_42") (pintype "passive"))
    )
    (net (code "227") (name "unconnected-(U2-NC-Pad43)") (class "Default")
      (node (ref "U2") (pin "43") (pinfunction "NC_43") (pintype "passive"))
    )
    (net (code "228") (name "unconnected-(U3-A1-Pad3)") (class "Default")
      (node (ref "U3") (pin "3") (pinfunction "A1_3") (pintype "passive"))
    )
    (net (code "229") (name "unconnected-(U3-A2-Pad4)") (class "Default")
      (node (ref "U3") (pin "4") (pinfunction "A2_4") (pintype "passive"))
    )
    (net (code "230") (name "unconnected-(U3-B1-Pad21)") (class "Default")
      (node (ref "U3") (pin "21") (pinfunction "B1_21") (pintype "passive"))
    )
    (net (code "231") (name "unconnected-(U3-B2-Pad20)") (class "Default")
      (node (ref "U3") (pin "20") (pinfunction "B2_20") (pintype "passive"))
    )
    (net (code "232") (name "unconnected-(U9-AUX_CL-Pad7)") (class "Default")
      (node (ref "U9") (pin "7") (pinfunction "AUX_CL_7") (pintype "passive"))
    )
    (net (code "233") (name "unconnected-(U9-AUX_DA-Pad21)") (class "Default")
      (node (ref "U9") (pin "21") (pinfunction "AUX_DA_21") (pintype "passive"))
    )
    (net (code "234") (name "unconnected-(U9-RES-Pad19)") (class "Default")
      (node (ref "U9") (pin "19") (pinfunction "RES_19") (pintype "passive"))
    )
    (net (code "235") (name "unconnected-(U16-NC-Pad3)") (class "Default")
      (node (ref "U16") (pin "3") (pinfunction "NC_3") (pintype "passive"))
    )
    (net (code "236") (name "unconnected-(U19-NC-Pad3)") (class "Default")
      (node (ref "U19") (pin "3") (pinfunction "NC_3") (pintype "passive"))
    )
    (net (code "237") (name "unconnected-(USB-ID-Pad4)") (class "Default")
      (node (ref "USB") (pin "4") (pinfunction "ID_4") (pintype "passive"))
    )
    (net (code "238") (name "unconnected-(u8-CAS-Pad11)") (class "Default")
      (node (ref "u8") (pin "11") (pinfunction "CAS_11") (pintype "passive"))
    )
    (net (code "239") (name "unconnected-(u8-EN-Pad22)") (class "Default")
      (node (ref "u8") (pin "22") (pinfunction "EN_22") (pintype "passive"))
    )
    (net (code "240") (name "unconnected-(u8-SHDN-Pad23)") (class "Default")
      (node (ref "u8") (pin "23") (pinfunction "SHDN_23") (pintype "passive"))
    )
  )
)
